# ra-08h_development_board_V1_0-20230228.net
KiCad netlist of a schematic drawn in EAGLE
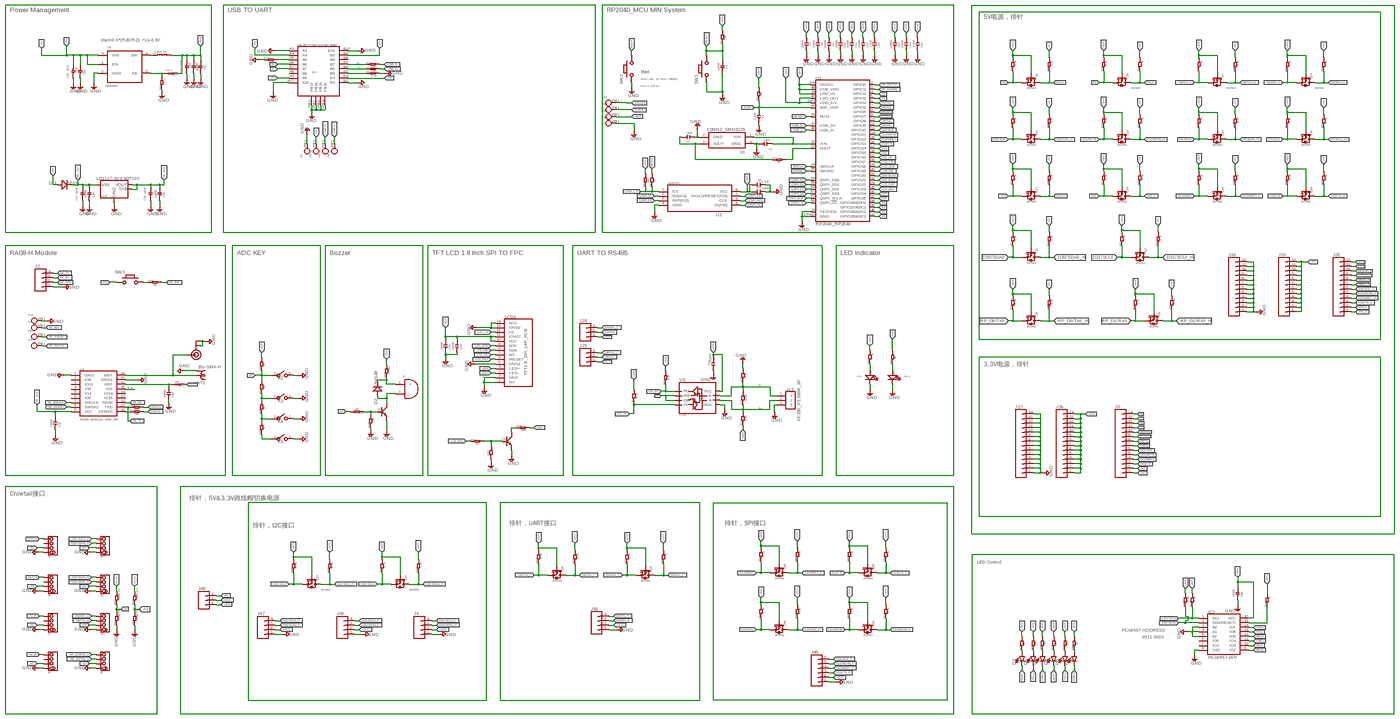
[diagram p0: schematic, sheet 1, overview]
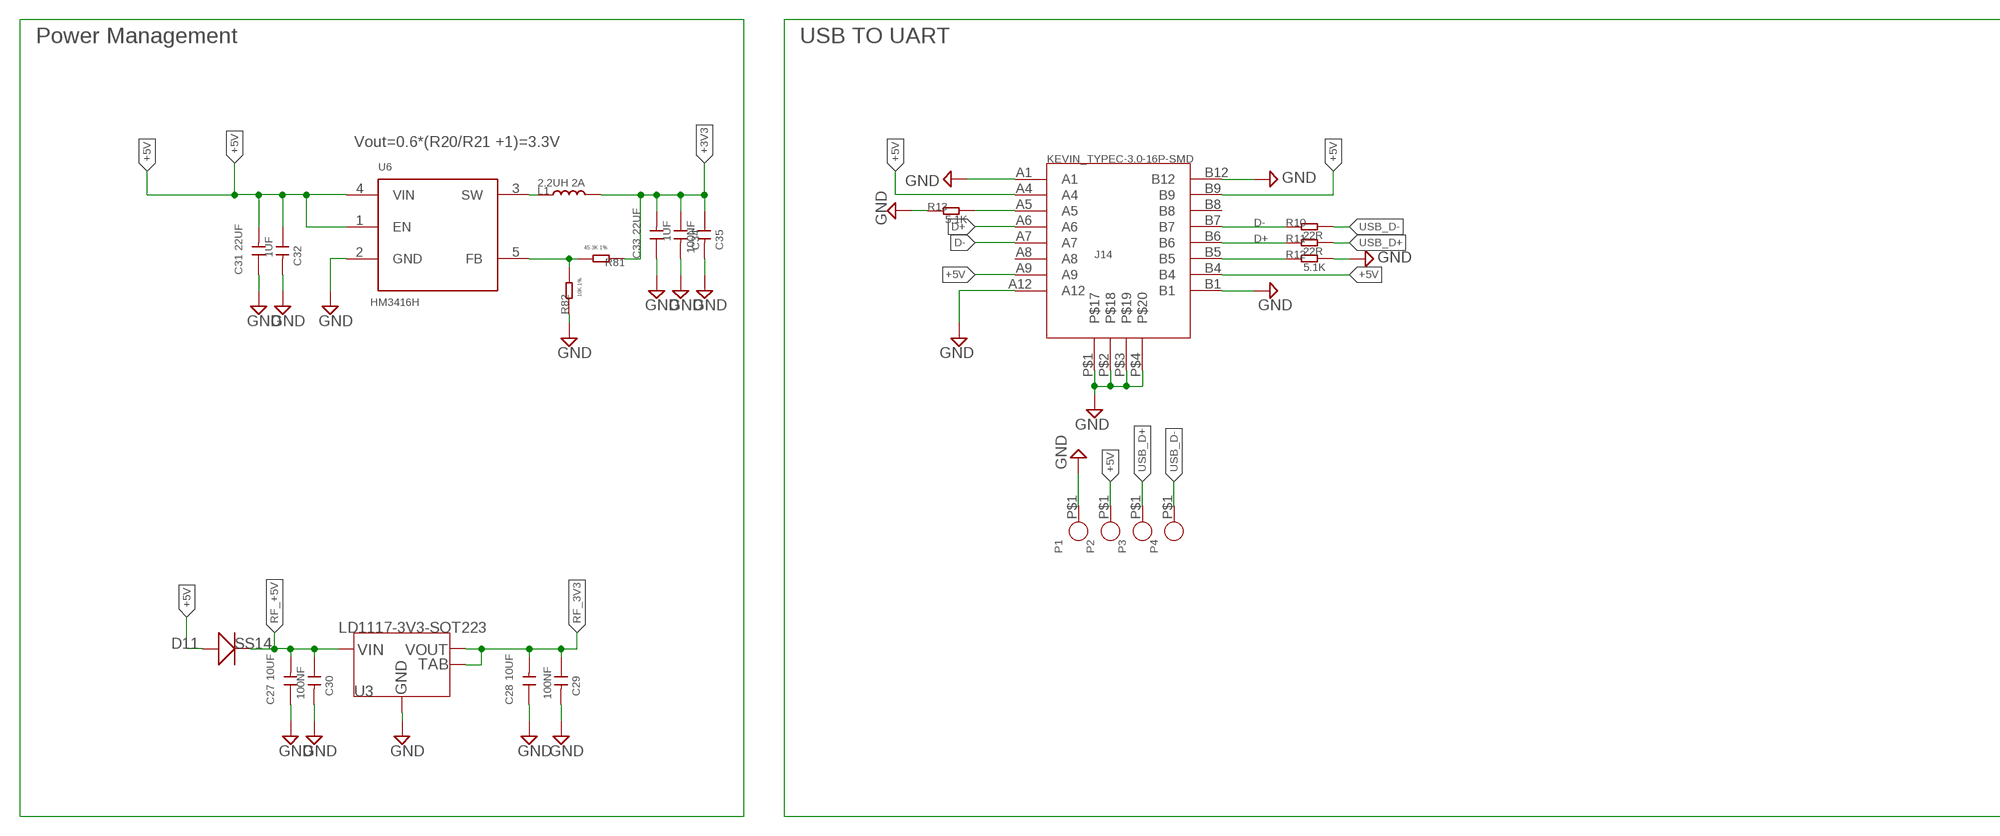
[diagram p1: schematic, sheet 1, part 1 of 6]
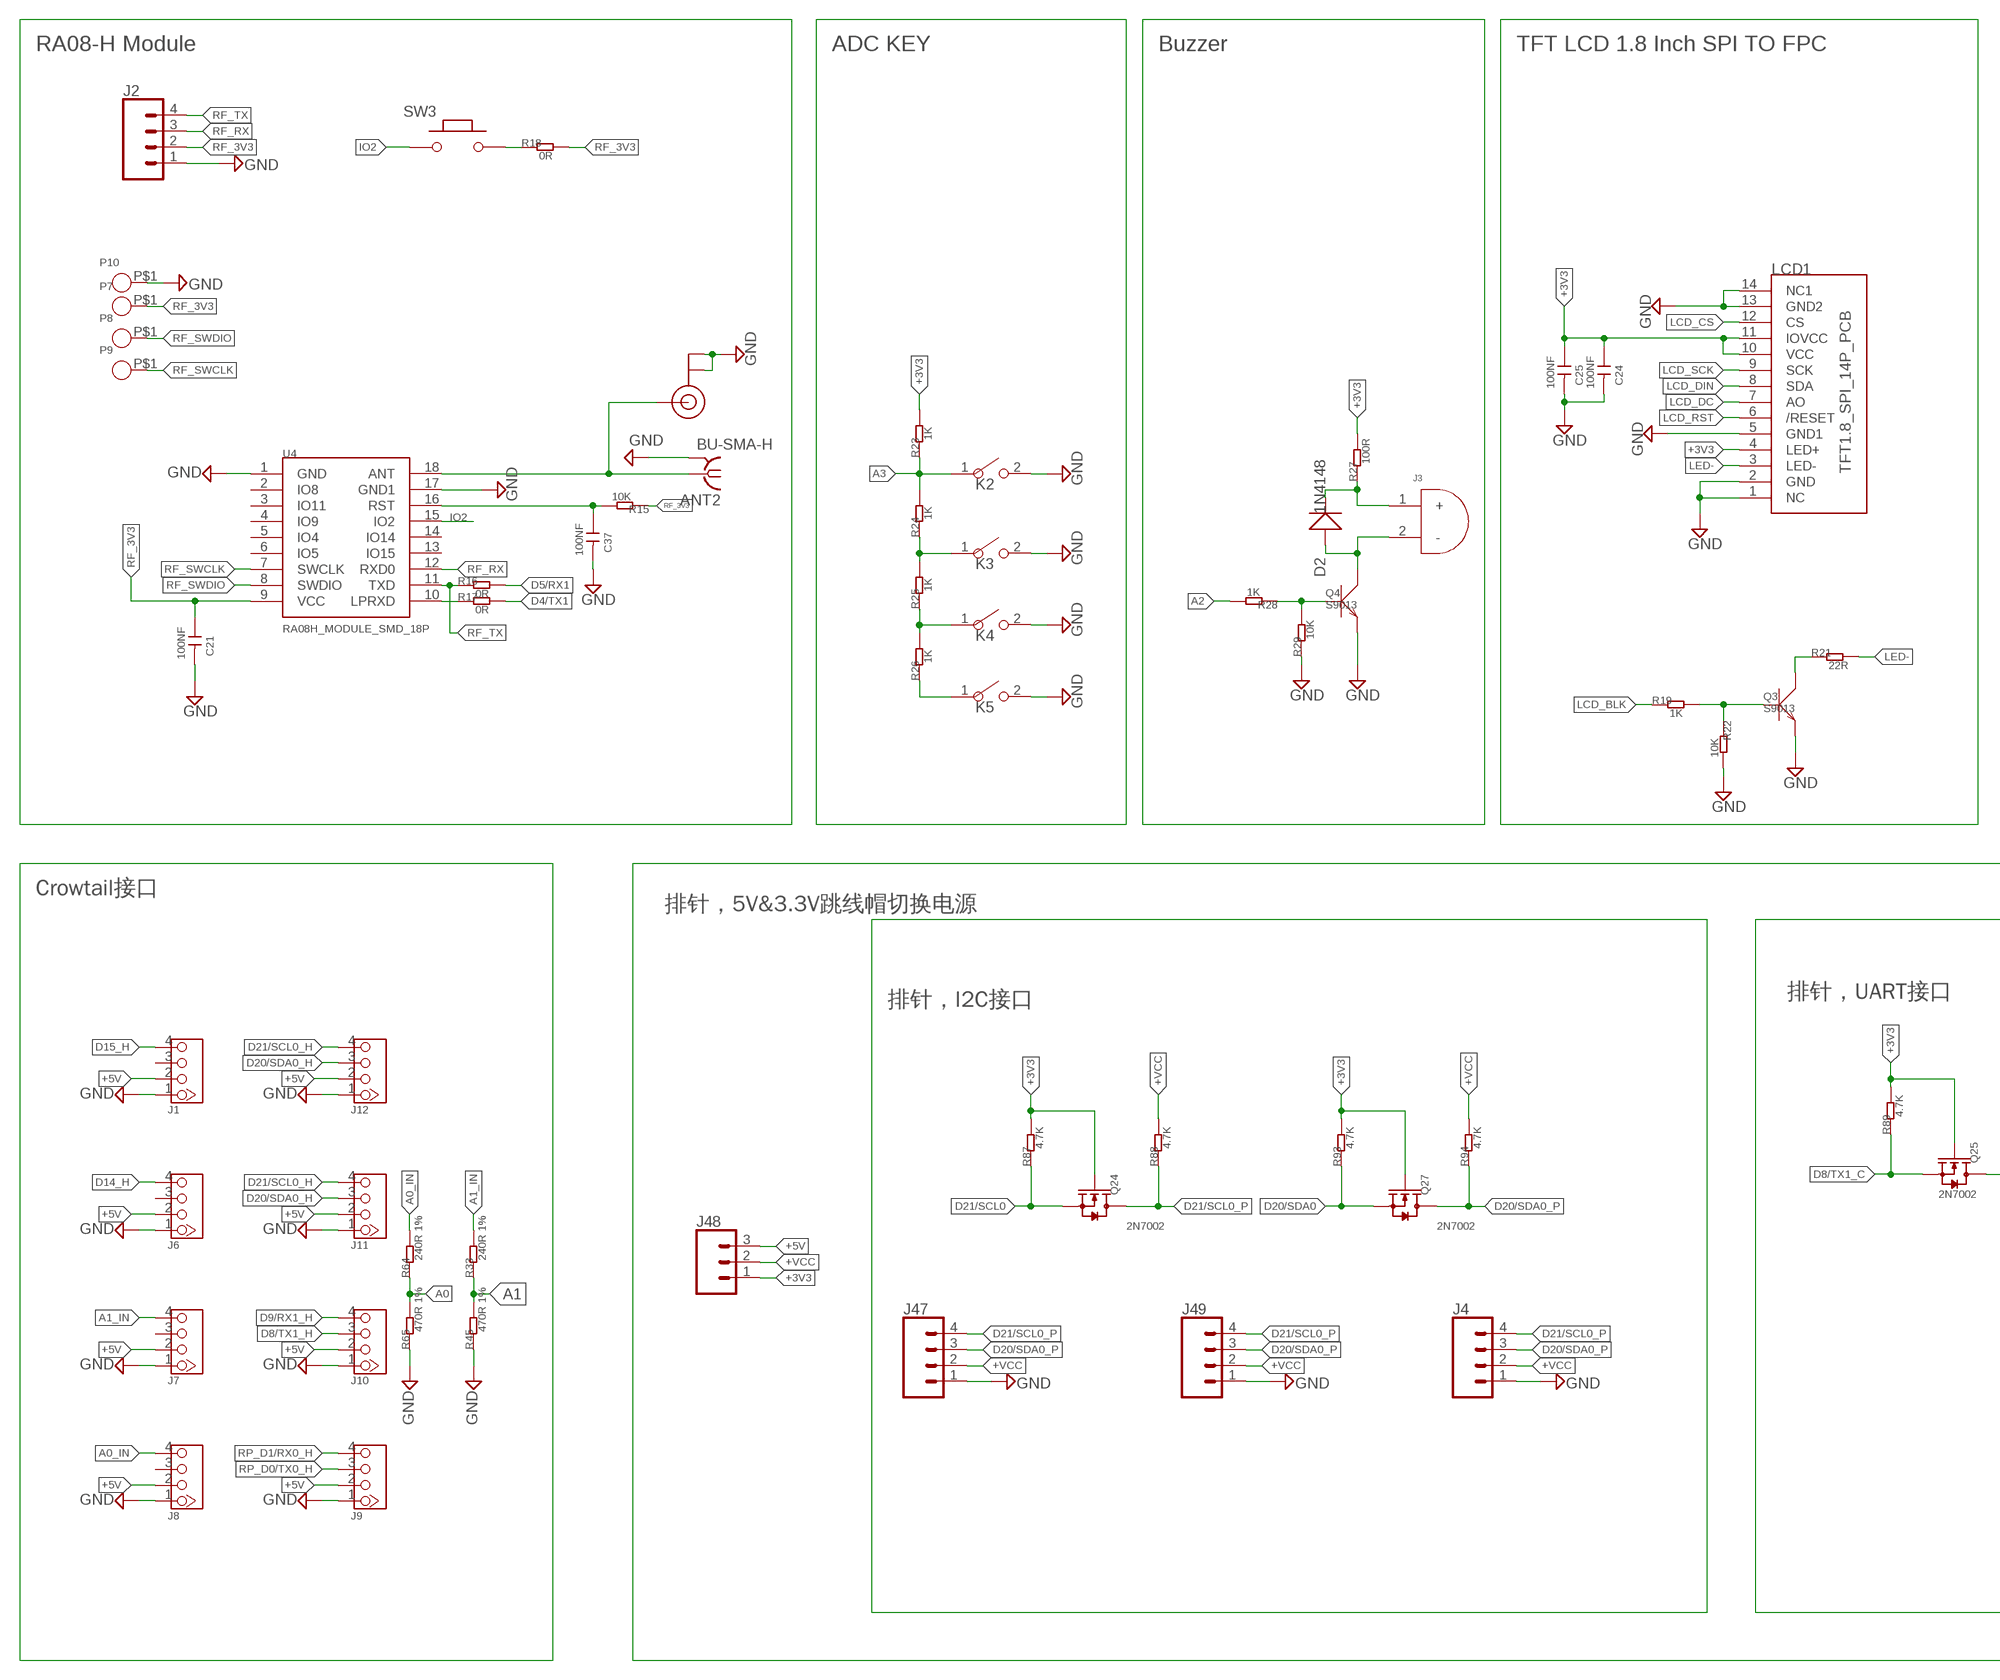
[diagram p2: schematic, sheet 1, part 2 of 6]
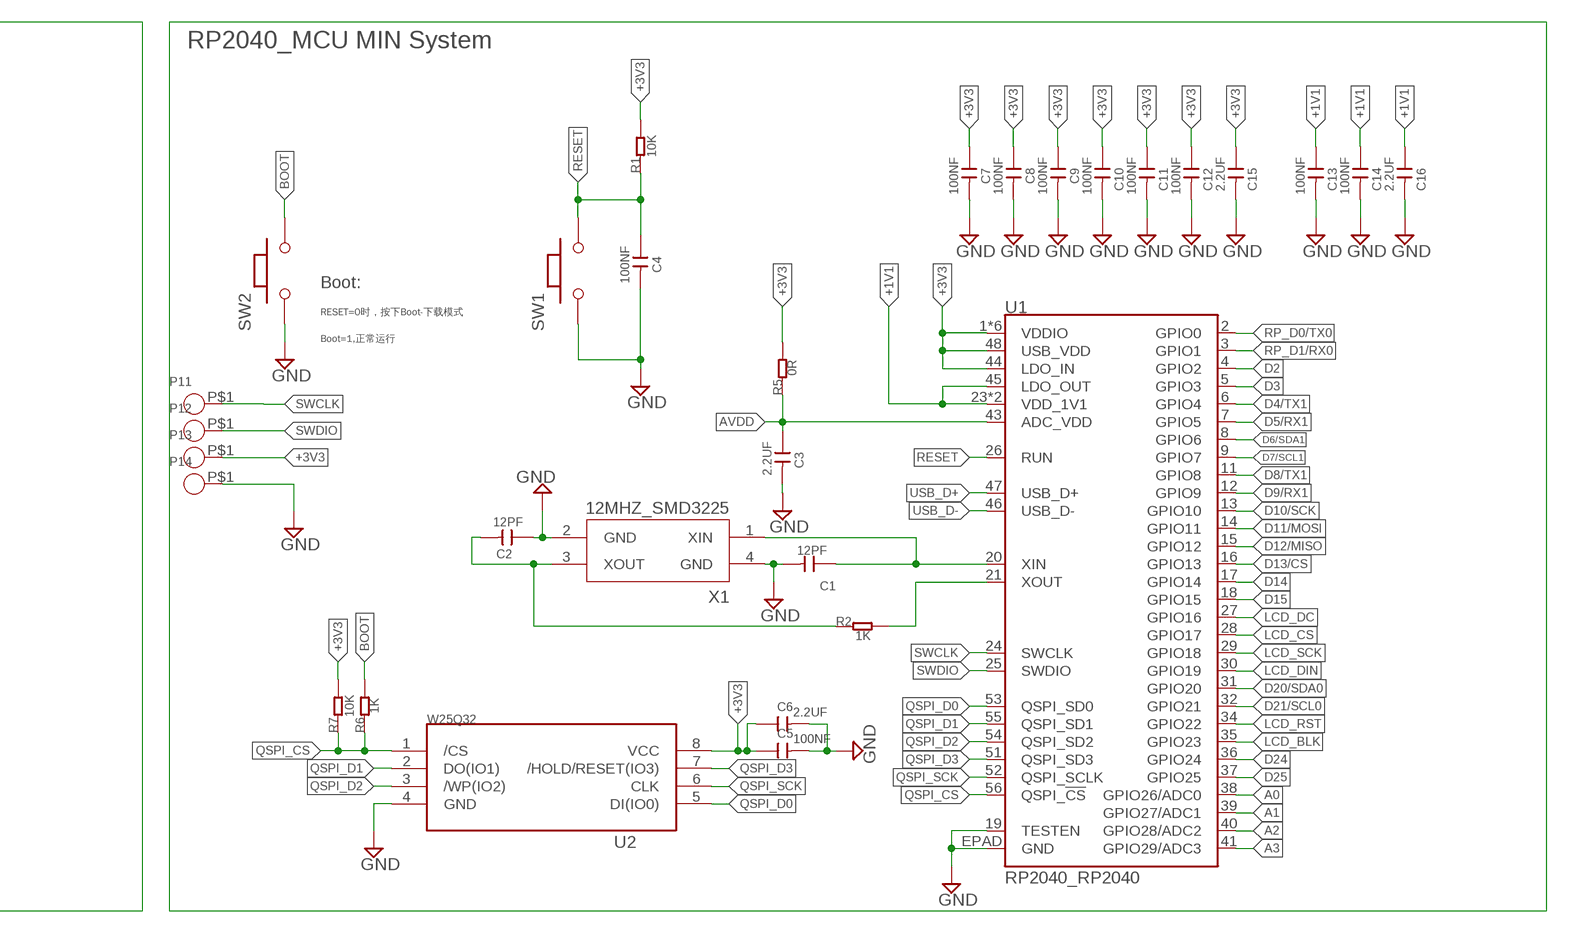
[diagram p3: schematic, sheet 1, part 3 of 6]
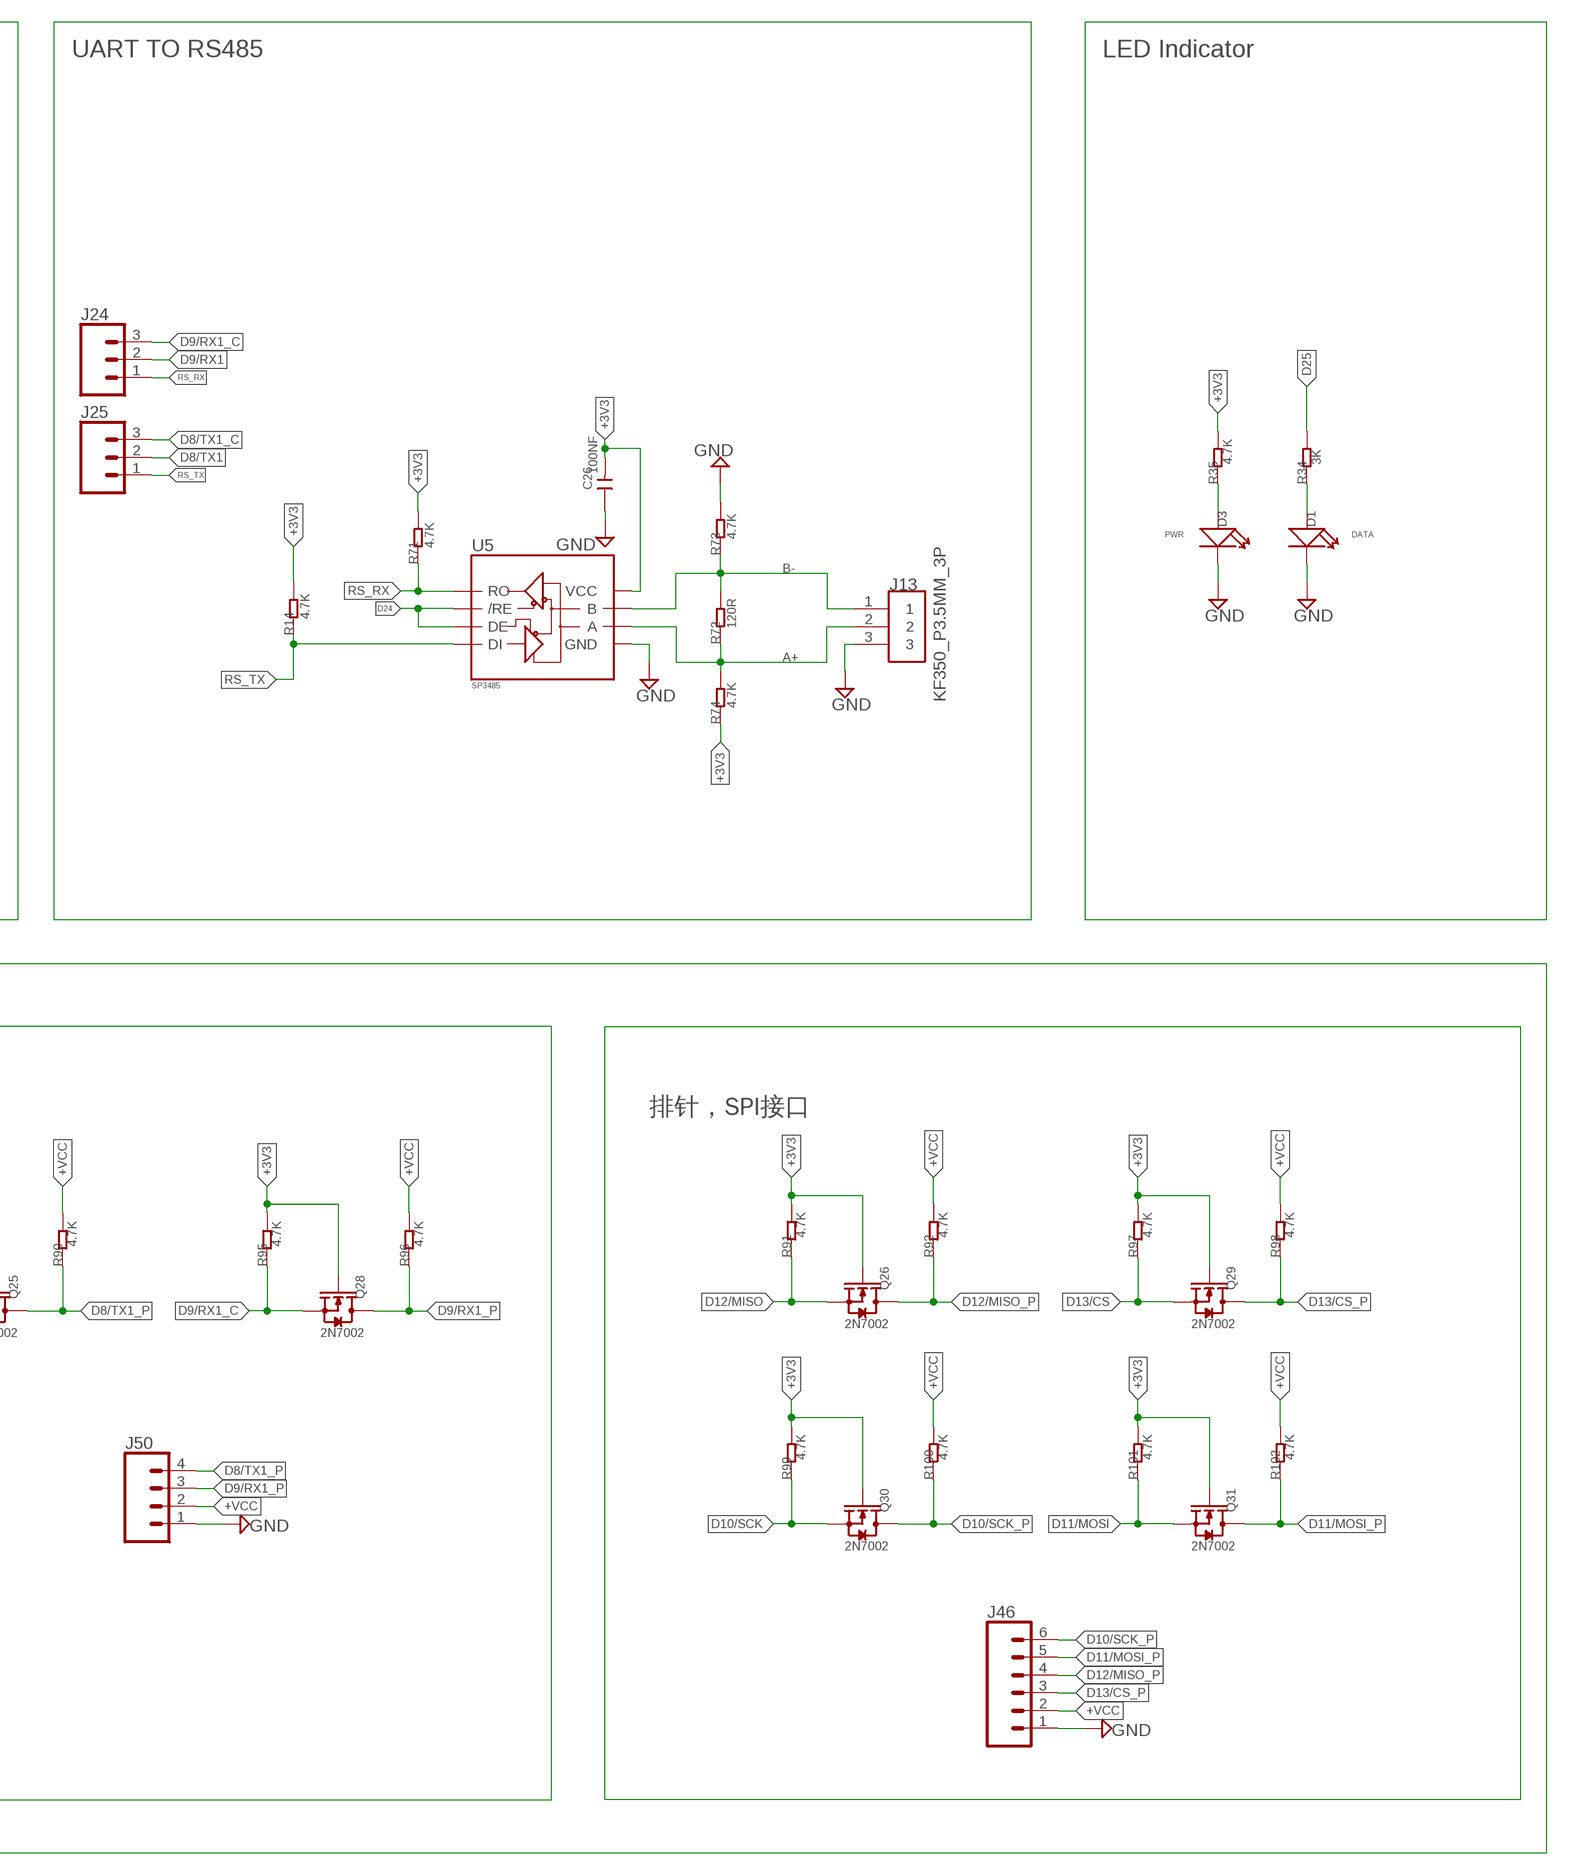
[diagram p4: schematic, sheet 1, part 4 of 6]
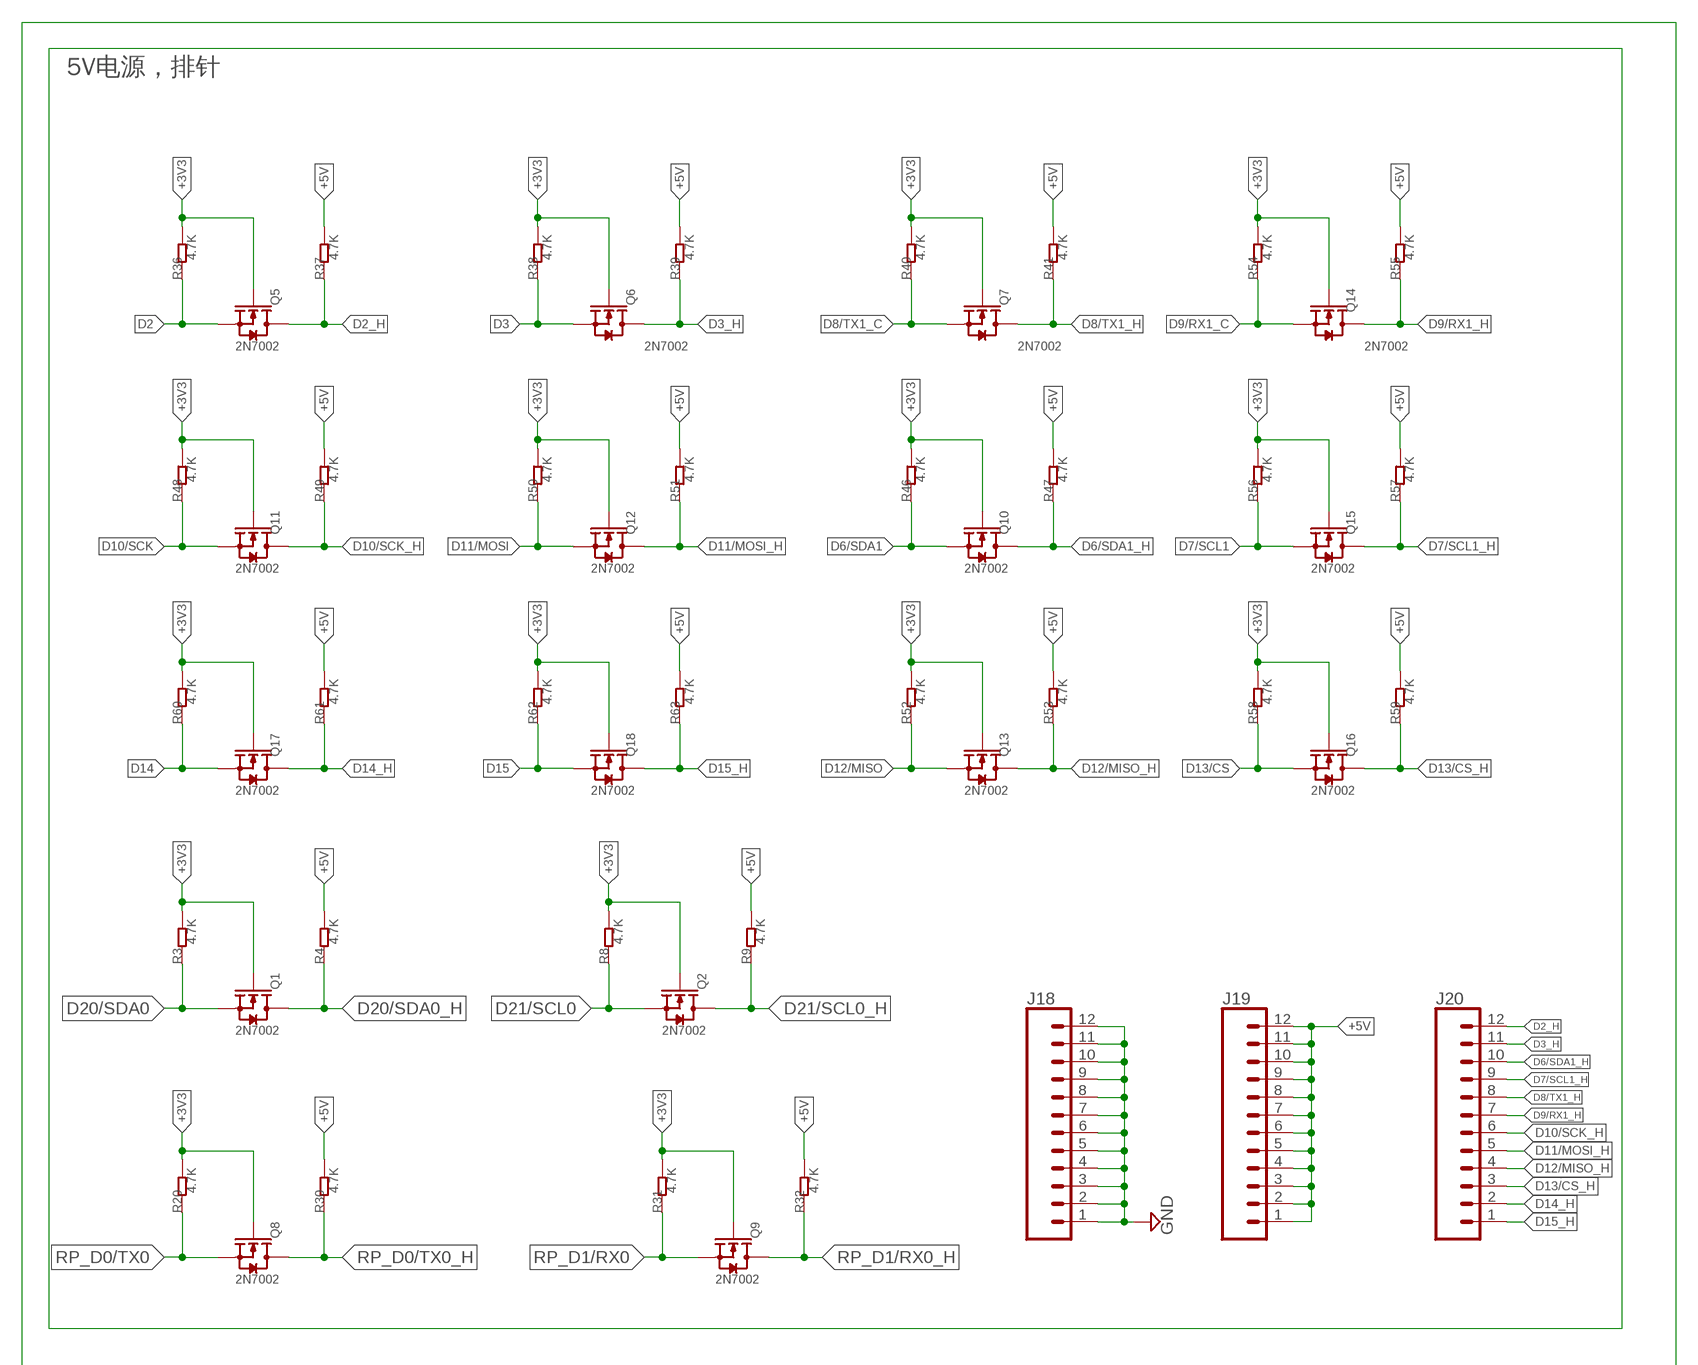
[diagram p5: schematic, sheet 1, part 5 of 6]
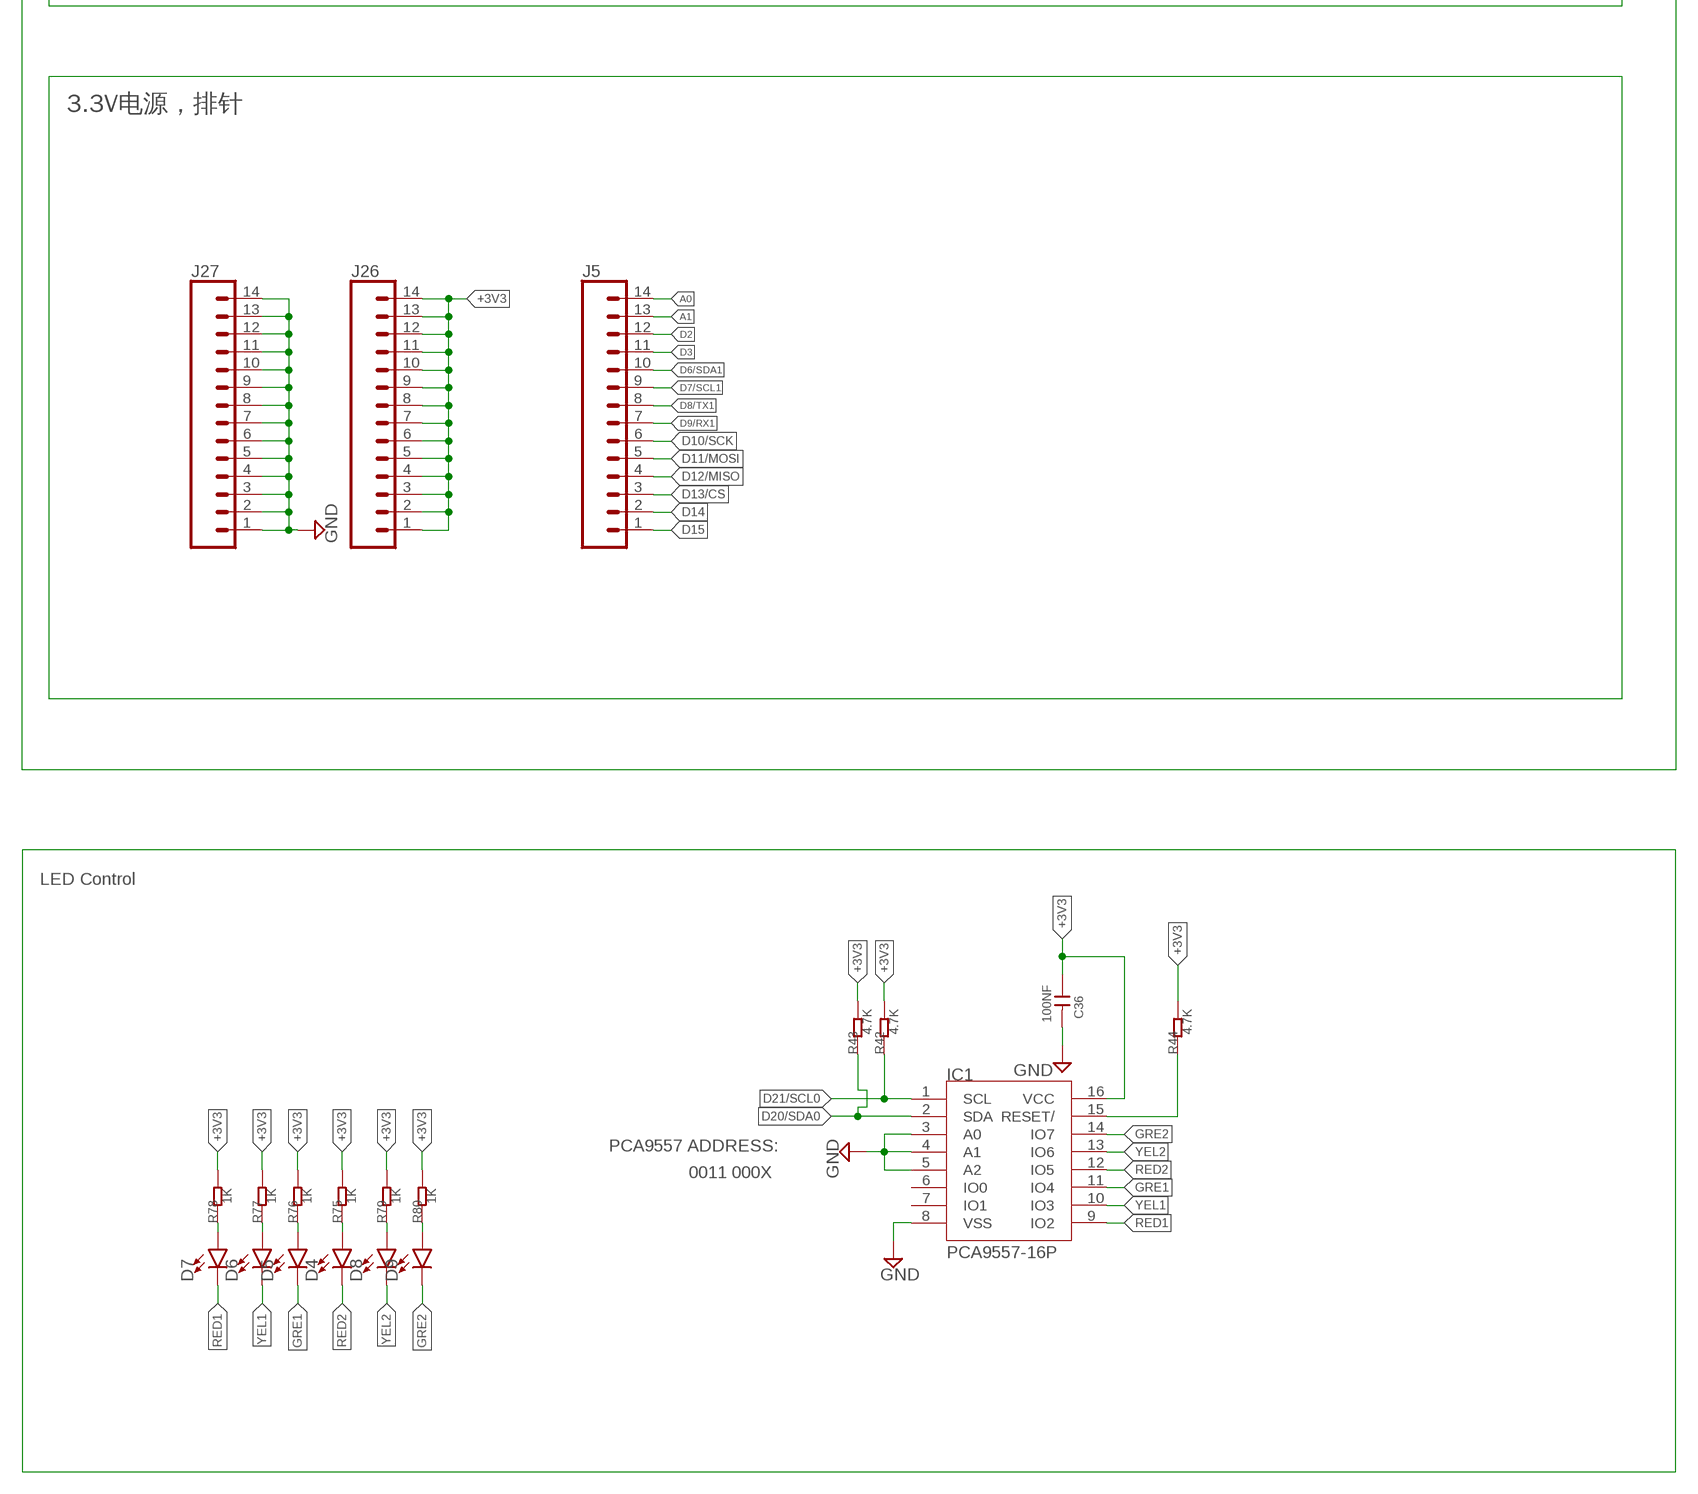
[diagram p6: schematic, sheet 1, part 6 of 6]

(export (version "E")
  (design (tool "Eeschema 10.0.6"))
  (components
    (comp (ref "ANT1")
      (value "SPARKFUN2_U.FL")
      (footprint "eagle-import:SPARKFUN2_U.FL")
      (libsource (lib "eagle-import") (part "SPARKFUN2_U.FL"))
    )
    (comp (ref "ANT2")
      (value "BU-SMA-H")
      (footprint "eagle-import:BU-SMA-H")
      (libsource (lib "eagle-import") (part "BU-SMA-H"))
    )
    (comp (ref "C1")
      (value "12PF")
      (footprint "eagle-import:A_XBJ_0603")
      (libsource (lib "eagle-import") (part "A_XBJ_C0603"))
    )
    (comp (ref "C2")
      (value "12PF")
      (footprint "eagle-import:A_XBJ_0603")
      (libsource (lib "eagle-import") (part "A_XBJ_C0603"))
    )
    (comp (ref "C3")
      (value "2.2UF")
      (footprint "eagle-import:A_XBJ_0603")
      (libsource (lib "eagle-import") (part "A_XBJ_C0603"))
    )
    (comp (ref "C4")
      (value "100NF")
      (footprint "eagle-import:A_XBJ_0603")
      (libsource (lib "eagle-import") (part "A_XBJ_C0603"))
    )
    (comp (ref "C5")
      (value "100NF")
      (footprint "eagle-import:A_XBJ_0603")
      (libsource (lib "eagle-import") (part "A_XBJ_C0603"))
    )
    (comp (ref "C6")
      (value "2.2UF")
      (footprint "eagle-import:A_XBJ_0603")
      (libsource (lib "eagle-import") (part "A_XBJ_C0603"))
    )
    (comp (ref "C7")
      (value "100NF")
      (footprint "eagle-import:A_XBJ_0603")
      (libsource (lib "eagle-import") (part "A_XBJ_C0603"))
    )
    (comp (ref "C8")
      (value "100NF")
      (footprint "eagle-import:A_XBJ_0603")
      (libsource (lib "eagle-import") (part "A_XBJ_C0603"))
    )
    (comp (ref "C9")
      (value "100NF")
      (footprint "eagle-import:A_XBJ_0603")
      (libsource (lib "eagle-import") (part "A_XBJ_C0603"))
    )
    (comp (ref "C10")
      (value "100NF")
      (footprint "eagle-import:A_XBJ_0603")
      (libsource (lib "eagle-import") (part "A_XBJ_C0603"))
    )
    (comp (ref "C11")
      (value "100NF")
      (footprint "eagle-import:A_XBJ_0603")
      (libsource (lib "eagle-import") (part "A_XBJ_C0603"))
    )
    (comp (ref "C12")
      (value "100NF")
      (footprint "eagle-import:A_XBJ_0603")
      (libsource (lib "eagle-import") (part "A_XBJ_C0603"))
    )
    (comp (ref "C13")
      (value "100NF")
      (footprint "eagle-import:A_XBJ_0603")
      (libsource (lib "eagle-import") (part "A_XBJ_C0603"))
    )
    (comp (ref "C14")
      (value "100NF")
      (footprint "eagle-import:A_XBJ_0603")
      (libsource (lib "eagle-import") (part "A_XBJ_C0603"))
    )
    (comp (ref "C15")
      (value "2.2UF")
      (footprint "eagle-import:A_XBJ_0603")
      (libsource (lib "eagle-import") (part "A_XBJ_C0603"))
    )
    (comp (ref "C16")
      (value "2.2UF")
      (footprint "eagle-import:A_XBJ_0603")
      (libsource (lib "eagle-import") (part "A_XBJ_C0603"))
    )
    (comp (ref "C21")
      (value "100NF")
      (footprint "eagle-import:A_XBJ_0603")
      (libsource (lib "eagle-import") (part "A_XBJ_C0603"))
    )
    (comp (ref "C24")
      (value "100NF")
      (footprint "eagle-import:A_XBJ_0603")
      (libsource (lib "eagle-import") (part "A_XBJ_C0603"))
    )
    (comp (ref "C25")
      (value "100NF")
      (footprint "eagle-import:A_XBJ_0603")
      (libsource (lib "eagle-import") (part "A_XBJ_C0603"))
    )
    (comp (ref "C26")
      (value "100NF")
      (footprint "eagle-import:A_XBJ_0603")
      (libsource (lib "eagle-import") (part "A_XBJ_C0603"))
    )
    (comp (ref "C27")
      (value "10UF")
      (footprint "eagle-import:A_XBJ_0805")
      (libsource (lib "eagle-import") (part "A_XBJ_C0805"))
    )
    (comp (ref "C28")
      (value "10UF")
      (footprint "eagle-import:A_XBJ_0805")
      (libsource (lib "eagle-import") (part "A_XBJ_C0805"))
    )
    (comp (ref "C29")
      (value "100NF")
      (footprint "eagle-import:A_XBJ_0603")
      (libsource (lib "eagle-import") (part "A_XBJ_C0603"))
    )
    (comp (ref "C30")
      (value "100NF")
      (footprint "eagle-import:A_XBJ_0603")
      (libsource (lib "eagle-import") (part "A_XBJ_C0603"))
    )
    (comp (ref "C31")
      (value "22UF")
      (footprint "eagle-import:A_XBJ_0805")
      (libsource (lib "eagle-import") (part "A_XBJ_C0805"))
    )
    (comp (ref "C32")
      (value "1UF")
      (footprint "eagle-import:A_XBJ_0603")
      (libsource (lib "eagle-import") (part "A_XBJ_C0603"))
    )
    (comp (ref "C33")
      (value "22UF")
      (footprint "eagle-import:A_XBJ_0805")
      (libsource (lib "eagle-import") (part "A_XBJ_C0805"))
    )
    (comp (ref "C34")
      (value "1UF")
      (footprint "eagle-import:A_XBJ_0603")
      (libsource (lib "eagle-import") (part "A_XBJ_C0603"))
    )
    (comp (ref "C35")
      (value "100NF")
      (footprint "eagle-import:A_XBJ_0603")
      (libsource (lib "eagle-import") (part "A_XBJ_C0603"))
    )
    (comp (ref "C36")
      (value "100NF")
      (footprint "eagle-import:A_XBJ_0603")
      (libsource (lib "eagle-import") (part "A_XBJ_C0603"))
    )
    (comp (ref "C37")
      (value "100NF")
      (footprint "eagle-import:A_XBJ_0603")
      (libsource (lib "eagle-import") (part "A_XBJ_C0603"))
    )
    (comp (ref "D1")
      (value "DISCRETE_007-LED0603")
      (footprint "eagle-import:DISCRETE_D0603")
      (libsource (lib "eagle-import") (part "DISCRETE_007-LED0603"))
    )
    (comp (ref "D2")
      (value "1N4148")
      (footprint "eagle-import:DISCRETE_DO-35-SMD")
      (libsource (lib "eagle-import") (part "DISCRETE_D1N4148-SMD"))
    )
    (comp (ref "D3")
      (value "DISCRETE_007-LED0603")
      (footprint "eagle-import:DISCRETE_D0603")
      (libsource (lib "eagle-import") (part "DISCRETE_007-LED0603"))
    )
    (comp (ref "D4")
      (value "LED-3MM-NO_SILK")
      (footprint "eagle-import:LED_3MM-NS")
      (libsource (lib "eagle-import") (part "LED-3MM-NO_SILK"))
    )
    (comp (ref "D5")
      (value "LED-3MM-NO_SILK")
      (footprint "eagle-import:LED_3MM-NS")
      (libsource (lib "eagle-import") (part "LED-3MM-NO_SILK"))
    )
    (comp (ref "D6")
      (value "LED-3MM-NO_SILK")
      (footprint "eagle-import:LED_3MM-NS")
      (libsource (lib "eagle-import") (part "LED-3MM-NO_SILK"))
    )
    (comp (ref "D7")
      (value "LED-3MM-NO_SILK")
      (footprint "eagle-import:LED_3MM-NS")
      (libsource (lib "eagle-import") (part "LED-3MM-NO_SILK"))
    )
    (comp (ref "D8")
      (value "LED-3MM-NO_SILK")
      (footprint "eagle-import:LED_3MM-NS")
      (libsource (lib "eagle-import") (part "LED-3MM-NO_SILK"))
    )
    (comp (ref "D9")
      (value "LED-3MM-NO_SILK")
      (footprint "eagle-import:LED_3MM-NS")
      (libsource (lib "eagle-import") (part "LED-3MM-NO_SILK"))
    )
    (comp (ref "D11")
      (value "SS14")
      (footprint "eagle-import:DISCRETE_D2010")
      (libsource (lib "eagle-import") (part "DISCRETE_DSMA"))
    )
    (comp (ref "IC1")
      (value "PCA9557-16P")
      (footprint "eagle-import:TSSOP16")
      (libsource (lib "eagle-import") (part "PCA9557-16P"))
    )
    (comp (ref "J1")
      (value "CONNECTER_TWIG_2.0")
      (footprint "eagle-import:CONNECTER_2.0_1X4")
      (libsource (lib "eagle-import") (part "CONNECTER_TWIG_2.0"))
    )
    (comp (ref "J2")
      (value "CONN_04PTH")
      (footprint "eagle-import:1X04")
      (libsource (lib "eagle-import") (part "CONN_04PTH"))
    )
    (comp (ref "J3")
      (value "A_XBJ_MLT-8530")
      (footprint "eagle-import:A_XBJ_MLT-8530")
      (libsource (lib "eagle-import") (part "A_XBJ_MLT-8530"))
    )
    (comp (ref "J4")
      (value "CONN_04PTH")
      (footprint "eagle-import:1X04")
      (libsource (lib "eagle-import") (part "CONN_04PTH"))
    )
    (comp (ref "J5")
      (value "CONN_14")
      (footprint "eagle-import:1X14")
      (libsource (lib "eagle-import") (part "CONN_14"))
    )
    (comp (ref "J6")
      (value "CONNECTER_TWIG_2.0")
      (footprint "eagle-import:CONNECTER_2.0_1X4")
      (libsource (lib "eagle-import") (part "CONNECTER_TWIG_2.0"))
    )
    (comp (ref "J7")
      (value "CONNECTER_TWIG_2.0")
      (footprint "eagle-import:CONNECTER_2.0_1X4")
      (libsource (lib "eagle-import") (part "CONNECTER_TWIG_2.0"))
    )
    (comp (ref "J8")
      (value "CONNECTER_TWIG_2.0")
      (footprint "eagle-import:CONNECTER_2.0_1X4")
      (libsource (lib "eagle-import") (part "CONNECTER_TWIG_2.0"))
    )
    (comp (ref "J9")
      (value "CONNECTER_TWIG_2.0")
      (footprint "eagle-import:CONNECTER_2.0_1X4")
      (libsource (lib "eagle-import") (part "CONNECTER_TWIG_2.0"))
    )
    (comp (ref "J10")
      (value "CONNECTER_TWIG_2.0")
      (footprint "eagle-import:CONNECTER_2.0_1X4")
      (libsource (lib "eagle-import") (part "CONNECTER_TWIG_2.0"))
    )
    (comp (ref "J11")
      (value "CONNECTER_TWIG_2.0")
      (footprint "eagle-import:CONNECTER_2.0_1X4")
      (libsource (lib "eagle-import") (part "CONNECTER_TWIG_2.0"))
    )
    (comp (ref "J12")
      (value "CONNECTER_TWIG_2.0")
      (footprint "eagle-import:CONNECTER_2.0_1X4")
      (libsource (lib "eagle-import") (part "CONNECTER_TWIG_2.0"))
    )
    (comp (ref "J13")
      (value "KF350_P3.5MM_3P")
      (footprint "eagle-import:KF350_P3.5MM_3P")
      (libsource (lib "eagle-import") (part "KF350_P3.5MM_3P"))
    )
    (comp (ref "J14")
      (value "KEVIN_TYPEC-3.0-16P-SMD")
      (footprint "eagle-import:KEVIN_3.0TYPEC-SMD")
      (libsource (lib "eagle-import") (part "KEVIN_TYPEC-3.0-16P-SMD"))
    )
    (comp (ref "J18")
      (value "CONN_12")
      (footprint "eagle-import:1X12")
      (libsource (lib "eagle-import") (part "CONN_12"))
    )
    (comp (ref "J19")
      (value "CONN_12")
      (footprint "eagle-import:1X12")
      (libsource (lib "eagle-import") (part "CONN_12"))
    )
    (comp (ref "J20")
      (value "CONN_12")
      (footprint "eagle-import:1X12")
      (libsource (lib "eagle-import") (part "CONN_12"))
    )
    (comp (ref "J24")
      (value "455-1750-1-ND")
      (footprint "eagle-import:1X03")
      (libsource (lib "eagle-import") (part "CONN_03"))
    )
    (comp (ref "J25")
      (value "455-1750-1-ND")
      (footprint "eagle-import:1X03")
      (libsource (lib "eagle-import") (part "CONN_03"))
    )
    (comp (ref "J26")
      (value "CONN_14")
      (footprint "eagle-import:1X14")
      (libsource (lib "eagle-import") (part "CONN_14"))
    )
    (comp (ref "J27")
      (value "CONN_14")
      (footprint "eagle-import:1X14")
      (libsource (lib "eagle-import") (part "CONN_14"))
    )
    (comp (ref "J46")
      (value "CONN_06SILK_FEMALE_PTH")
      (footprint "eagle-import:1X06")
      (libsource (lib "eagle-import") (part "CONN_06SILK_FEMALE_PTH"))
    )
    (comp (ref "J47")
      (value "CONN_04PTH")
      (footprint "eagle-import:1X04")
      (libsource (lib "eagle-import") (part "CONN_04PTH"))
    )
    (comp (ref "J48")
      (value "455-1750-1-ND")
      (footprint "eagle-import:1X03")
      (libsource (lib "eagle-import") (part "CONN_03"))
    )
    (comp (ref "J49")
      (value "CONN_04PTH")
      (footprint "eagle-import:1X04")
      (libsource (lib "eagle-import") (part "CONN_04PTH"))
    )
    (comp (ref "J50")
      (value "CONN_04PTH")
      (footprint "eagle-import:1X04")
      (libsource (lib "eagle-import") (part "CONN_04PTH"))
    )
    (comp (ref "K2")
      (value "CROWBO_KEY_2PIN_6.5X3.5")
      (footprint "eagle-import:CROWBOT_-V1.2-20220713_CROWBOT-V1.1库_KEY_EN_2PIN_B_W")
      (libsource (lib "eagle-import") (part "CROWBO_KEY_2PIN_6.5X3.5"))
    )
    (comp (ref "K3")
      (value "CROWBO_KEY_2PIN_6.5X3.5")
      (footprint "eagle-import:CROWBOT_-V1.2-20220713_CROWBOT-V1.1库_KEY_EN_2PIN_B_W")
      (libsource (lib "eagle-import") (part "CROWBO_KEY_2PIN_6.5X3.5"))
    )
    (comp (ref "K4")
      (value "CROWBO_KEY_2PIN_6.5X3.5")
      (footprint "eagle-import:CROWBOT_-V1.2-20220713_CROWBOT-V1.1库_KEY_EN_2PIN_B_W")
      (libsource (lib "eagle-import") (part "CROWBO_KEY_2PIN_6.5X3.5"))
    )
    (comp (ref "K5")
      (value "CROWBO_KEY_2PIN_6.5X3.5")
      (footprint "eagle-import:CROWBOT_-V1.2-20220713_CROWBOT-V1.1库_KEY_EN_2PIN_B_W")
      (libsource (lib "eagle-import") (part "CROWBO_KEY_2PIN_6.5X3.5"))
    )
    (comp (ref "L1")
      (value "2.2UH 2A")
      (footprint "eagle-import:CROWPI_POW_L773")
      (libsource (lib "eagle-import") (part "DISCRETE_LL773"))
    )
    (comp (ref "LCD1")
      (value "TFT1.8_SPI_14P_PCB")
      (footprint "eagle-import:TFF1.8_SPI_14P_PCB")
      (libsource (lib "eagle-import") (part "TFT1.8_SPI_14P_PCB"))
    )
    (comp (ref "P1")
      (value "CROWPI_POW_PADPAD-1.0MM")
      (footprint "eagle-import:CROWPI_POW_PAD-1.0MM")
      (libsource (lib "eagle-import") (part "CROWPI_POW_PADPAD-1.0MM"))
    )
    (comp (ref "P2")
      (value "CROWPI_POW_PADPAD-1.0MM")
      (footprint "eagle-import:CROWPI_POW_PAD-1.0MM")
      (libsource (lib "eagle-import") (part "CROWPI_POW_PADPAD-1.0MM"))
    )
    (comp (ref "P3")
      (value "CROWPI_POW_PADPAD-1.0MM")
      (footprint "eagle-import:CROWPI_POW_PAD-1.0MM")
      (libsource (lib "eagle-import") (part "CROWPI_POW_PADPAD-1.0MM"))
    )
    (comp (ref "P4")
      (value "CROWPI_POW_PADPAD-1.0MM")
      (footprint "eagle-import:CROWPI_POW_PAD-1.0MM")
      (libsource (lib "eagle-import") (part "CROWPI_POW_PADPAD-1.0MM"))
    )
    (comp (ref "P7")
      (value "CROWPI_POW_PADPAD-1.0MM")
      (footprint "eagle-import:CROWPI_POW_PAD-1.0MM")
      (libsource (lib "eagle-import") (part "CROWPI_POW_PADPAD-1.0MM"))
    )
    (comp (ref "P8")
      (value "CROWPI_POW_PADPAD-1.0MM")
      (footprint "eagle-import:CROWPI_POW_PAD-1.0MM")
      (libsource (lib "eagle-import") (part "CROWPI_POW_PADPAD-1.0MM"))
    )
    (comp (ref "P9")
      (value "CROWPI_POW_PADPAD-1.0MM")
      (footprint "eagle-import:CROWPI_POW_PAD-1.0MM")
      (libsource (lib "eagle-import") (part "CROWPI_POW_PADPAD-1.0MM"))
    )
    (comp (ref "P10")
      (value "CROWPI_POW_PADPAD-1.0MM")
      (footprint "eagle-import:CROWPI_POW_PAD-1.0MM")
      (libsource (lib "eagle-import") (part "CROWPI_POW_PADPAD-1.0MM"))
    )
    (comp (ref "P11")
      (value "CROWPI_POW_PADPAD-1.0MM")
      (footprint "eagle-import:CROWPI_POW_PAD-1.0MM")
      (libsource (lib "eagle-import") (part "CROWPI_POW_PADPAD-1.0MM"))
    )
    (comp (ref "P12")
      (value "CROWPI_POW_PADPAD-1.0MM")
      (footprint "eagle-import:CROWPI_POW_PAD-1.0MM")
      (libsource (lib "eagle-import") (part "CROWPI_POW_PADPAD-1.0MM"))
    )
    (comp (ref "P13")
      (value "CROWPI_POW_PADPAD-1.0MM")
      (footprint "eagle-import:CROWPI_POW_PAD-1.0MM")
      (libsource (lib "eagle-import") (part "CROWPI_POW_PADPAD-1.0MM"))
    )
    (comp (ref "P14")
      (value "CROWPI_POW_PADPAD-1.0MM")
      (footprint "eagle-import:CROWPI_POW_PAD-1.0MM")
      (libsource (lib "eagle-import") (part "CROWPI_POW_PADPAD-1.0MM"))
    )
    (comp (ref "Q1")
      (value "2N7002")
      (footprint "eagle-import:DISCRETE_SOT23")
      (libsource (lib "eagle-import") (part "DISCRETE_MOSFET-NSOT23"))
    )
    (comp (ref "Q2")
      (value "2N7002")
      (footprint "eagle-import:DISCRETE_SOT23")
      (libsource (lib "eagle-import") (part "DISCRETE_MOSFET-NSOT23"))
    )
    (comp (ref "Q3")
      (value "S9013")
      (footprint "eagle-import:DISCRETE_SOT23$1")
      (libsource (lib "eagle-import") (part "DISCRETE_TRANSISTOR-NPN-SOT23"))
    )
    (comp (ref "Q4")
      (value "S9013")
      (footprint "eagle-import:DISCRETE_SOT23$1")
      (libsource (lib "eagle-import") (part "DISCRETE_TRANSISTOR-NPN-SOT23"))
    )
    (comp (ref "Q5")
      (value "2N7002")
      (footprint "eagle-import:DISCRETE_SOT23")
      (libsource (lib "eagle-import") (part "DISCRETE_MOSFET-NSOT23"))
    )
    (comp (ref "Q6")
      (value "2N7002")
      (footprint "eagle-import:DISCRETE_SOT23")
      (libsource (lib "eagle-import") (part "DISCRETE_MOSFET-NSOT23"))
    )
    (comp (ref "Q7")
      (value "2N7002")
      (footprint "eagle-import:DISCRETE_SOT23")
      (libsource (lib "eagle-import") (part "DISCRETE_MOSFET-NSOT23"))
    )
    (comp (ref "Q8")
      (value "2N7002")
      (footprint "eagle-import:DISCRETE_SOT23")
      (libsource (lib "eagle-import") (part "DISCRETE_MOSFET-NSOT23"))
    )
    (comp (ref "Q9")
      (value "2N7002")
      (footprint "eagle-import:DISCRETE_SOT23")
      (libsource (lib "eagle-import") (part "DISCRETE_MOSFET-NSOT23"))
    )
    (comp (ref "Q10")
      (value "2N7002")
      (footprint "eagle-import:DISCRETE_SOT23")
      (libsource (lib "eagle-import") (part "DISCRETE_MOSFET-NSOT23"))
    )
    (comp (ref "Q11")
      (value "2N7002")
      (footprint "eagle-import:DISCRETE_SOT23")
      (libsource (lib "eagle-import") (part "DISCRETE_MOSFET-NSOT23"))
    )
    (comp (ref "Q12")
      (value "2N7002")
      (footprint "eagle-import:DISCRETE_SOT23")
      (libsource (lib "eagle-import") (part "DISCRETE_MOSFET-NSOT23"))
    )
    (comp (ref "Q13")
      (value "2N7002")
      (footprint "eagle-import:DISCRETE_SOT23")
      (libsource (lib "eagle-import") (part "DISCRETE_MOSFET-NSOT23"))
    )
    (comp (ref "Q14")
      (value "2N7002")
      (footprint "eagle-import:DISCRETE_SOT23")
      (libsource (lib "eagle-import") (part "DISCRETE_MOSFET-NSOT23"))
    )
    (comp (ref "Q15")
      (value "2N7002")
      (footprint "eagle-import:DISCRETE_SOT23")
      (libsource (lib "eagle-import") (part "DISCRETE_MOSFET-NSOT23"))
    )
    (comp (ref "Q16")
      (value "2N7002")
      (footprint "eagle-import:DISCRETE_SOT23")
      (libsource (lib "eagle-import") (part "DISCRETE_MOSFET-NSOT23"))
    )
    (comp (ref "Q17")
      (value "2N7002")
      (footprint "eagle-import:DISCRETE_SOT23")
      (libsource (lib "eagle-import") (part "DISCRETE_MOSFET-NSOT23"))
    )
    (comp (ref "Q18")
      (value "2N7002")
      (footprint "eagle-import:DISCRETE_SOT23")
      (libsource (lib "eagle-import") (part "DISCRETE_MOSFET-NSOT23"))
    )
    (comp (ref "Q24")
      (value "2N7002")
      (footprint "eagle-import:DISCRETE_SOT23")
      (libsource (lib "eagle-import") (part "DISCRETE_MOSFET-NSOT23"))
    )
    (comp (ref "Q25")
      (value "2N7002")
      (footprint "eagle-import:DISCRETE_SOT23")
      (libsource (lib "eagle-import") (part "DISCRETE_MOSFET-NSOT23"))
    )
    (comp (ref "Q26")
      (value "2N7002")
      (footprint "eagle-import:DISCRETE_SOT23")
      (libsource (lib "eagle-import") (part "DISCRETE_MOSFET-NSOT23"))
    )
    (comp (ref "Q27")
      (value "2N7002")
      (footprint "eagle-import:DISCRETE_SOT23")
      (libsource (lib "eagle-import") (part "DISCRETE_MOSFET-NSOT23"))
    )
    (comp (ref "Q28")
      (value "2N7002")
      (footprint "eagle-import:DISCRETE_SOT23")
      (libsource (lib "eagle-import") (part "DISCRETE_MOSFET-NSOT23"))
    )
    (comp (ref "Q29")
      (value "2N7002")
      (footprint "eagle-import:DISCRETE_SOT23")
      (libsource (lib "eagle-import") (part "DISCRETE_MOSFET-NSOT23"))
    )
    (comp (ref "Q30")
      (value "2N7002")
      (footprint "eagle-import:DISCRETE_SOT23")
      (libsource (lib "eagle-import") (part "DISCRETE_MOSFET-NSOT23"))
    )
    (comp (ref "Q31")
      (value "2N7002")
      (footprint "eagle-import:DISCRETE_SOT23")
      (libsource (lib "eagle-import") (part "DISCRETE_MOSFET-NSOT23"))
    )
    (comp (ref "R1")
      (value "10K")
      (footprint "eagle-import:DISCRETE_R0603")
      (libsource (lib "eagle-import") (part "DISCRETE_R-0603"))
    )
    (comp (ref "R2")
      (value "1K")
      (footprint "eagle-import:DISCRETE_R0603")
      (libsource (lib "eagle-import") (part "DISCRETE_R-0603"))
    )
    (comp (ref "R3")
      (value "4.7K")
      (footprint "eagle-import:DISCRETE_R0603")
      (libsource (lib "eagle-import") (part "DISCRETE_R-0603"))
    )
    (comp (ref "R4")
      (value "4.7K")
      (footprint "eagle-import:DISCRETE_R0603")
      (libsource (lib "eagle-import") (part "DISCRETE_R-0603"))
    )
    (comp (ref "R5")
      (value "0R")
      (footprint "eagle-import:DISCRETE_R0603")
      (libsource (lib "eagle-import") (part "DISCRETE_R-0603"))
    )
    (comp (ref "R6")
      (value "1K")
      (footprint "eagle-import:DISCRETE_R0603")
      (libsource (lib "eagle-import") (part "DISCRETE_R-0603"))
    )
    (comp (ref "R7")
      (value "10K")
      (footprint "eagle-import:DISCRETE_R0603")
      (libsource (lib "eagle-import") (part "DISCRETE_R-0603"))
    )
    (comp (ref "R8")
      (value "4.7K")
      (footprint "eagle-import:DISCRETE_R0603")
      (libsource (lib "eagle-import") (part "DISCRETE_R-0603"))
    )
    (comp (ref "R9")
      (value "4.7K")
      (footprint "eagle-import:DISCRETE_R0603")
      (libsource (lib "eagle-import") (part "DISCRETE_R-0603"))
    )
    (comp (ref "R10")
      (value "22R")
      (footprint "eagle-import:DISCRETE_R0603")
      (libsource (lib "eagle-import") (part "DISCRETE_R-0603"))
    )
    (comp (ref "R11")
      (value "22R")
      (footprint "eagle-import:DISCRETE_R0603")
      (libsource (lib "eagle-import") (part "DISCRETE_R-0603"))
    )
    (comp (ref "R12")
      (value "5.1K")
      (footprint "eagle-import:DISCRETE_R0603")
      (libsource (lib "eagle-import") (part "DISCRETE_R-0603"))
    )
    (comp (ref "R13")
      (value "5.1K")
      (footprint "eagle-import:DISCRETE_R0603")
      (libsource (lib "eagle-import") (part "DISCRETE_R-0603"))
    )
    (comp (ref "R14")
      (value "4.7K")
      (footprint "eagle-import:DISCRETE_R0603")
      (libsource (lib "eagle-import") (part "DISCRETE_R-0603"))
    )
    (comp (ref "R15")
      (value "10K")
      (footprint "eagle-import:DISCRETE_R0603")
      (libsource (lib "eagle-import") (part "DISCRETE_R-0603"))
    )
    (comp (ref "R16")
      (value "0R")
      (footprint "eagle-import:DISCRETE_R0603")
      (libsource (lib "eagle-import") (part "DISCRETE_R-0603"))
    )
    (comp (ref "R17")
      (value "0R")
      (footprint "eagle-import:DISCRETE_R0603")
      (libsource (lib "eagle-import") (part "DISCRETE_R-0603"))
    )
    (comp (ref "R18")
      (value "0R")
      (footprint "eagle-import:DISCRETE_R0603")
      (libsource (lib "eagle-import") (part "DISCRETE_R-0603"))
    )
    (comp (ref "R19")
      (value "1K")
      (footprint "eagle-import:DISCRETE_R0603")
      (libsource (lib "eagle-import") (part "DISCRETE_R-0603"))
    )
    (comp (ref "R20")
      (value "4.7K")
      (footprint "eagle-import:DISCRETE_R0603")
      (libsource (lib "eagle-import") (part "DISCRETE_R-0603"))
    )
    (comp (ref "R21")
      (value "22R")
      (footprint "eagle-import:DISCRETE_R0603")
      (libsource (lib "eagle-import") (part "DISCRETE_R-0603"))
    )
    (comp (ref "R22")
      (value "10K")
      (footprint "eagle-import:DISCRETE_R0603")
      (libsource (lib "eagle-import") (part "DISCRETE_R-0603"))
    )
    (comp (ref "R23")
      (value "1K")
      (footprint "eagle-import:DISCRETE_R0603")
      (libsource (lib "eagle-import") (part "DISCRETE_R-0603"))
    )
    (comp (ref "R24")
      (value "1K")
      (footprint "eagle-import:DISCRETE_R0603")
      (libsource (lib "eagle-import") (part "DISCRETE_R-0603"))
    )
    (comp (ref "R25")
      (value "1K")
      (footprint "eagle-import:DISCRETE_R0603")
      (libsource (lib "eagle-import") (part "DISCRETE_R-0603"))
    )
    (comp (ref "R26")
      (value "1K")
      (footprint "eagle-import:DISCRETE_R0603")
      (libsource (lib "eagle-import") (part "DISCRETE_R-0603"))
    )
    (comp (ref "R27")
      (value "100R")
      (footprint "eagle-import:DISCRETE_R0603")
      (libsource (lib "eagle-import") (part "DISCRETE_R-0603"))
    )
    (comp (ref "R28")
      (value "1K")
      (footprint "eagle-import:DISCRETE_R0603")
      (libsource (lib "eagle-import") (part "DISCRETE_R-0603"))
    )
    (comp (ref "R29")
      (value "10K")
      (footprint "eagle-import:DISCRETE_R0603")
      (libsource (lib "eagle-import") (part "DISCRETE_R-0603"))
    )
    (comp (ref "R30")
      (value "4.7K")
      (footprint "eagle-import:DISCRETE_R0603")
      (libsource (lib "eagle-import") (part "DISCRETE_R-0603"))
    )
    (comp (ref "R31")
      (value "4.7K")
      (footprint "eagle-import:DISCRETE_R0603")
      (libsource (lib "eagle-import") (part "DISCRETE_R-0603"))
    )
    (comp (ref "R32")
      (value "4.7K")
      (footprint "eagle-import:DISCRETE_R0603")
      (libsource (lib "eagle-import") (part "DISCRETE_R-0603"))
    )
    (comp (ref "R33")
      (value "240R 1%")
      (footprint "eagle-import:DISCRETE_R0603")
      (libsource (lib "eagle-import") (part "DISCRETE_R-0603"))
    )
    (comp (ref "R34")
      (value "3K")
      (footprint "eagle-import:DISCRETE_R0603")
      (libsource (lib "eagle-import") (part "DISCRETE_R-0603"))
    )
    (comp (ref "R35")
      (value "4.7K")
      (footprint "eagle-import:DISCRETE_R0603")
      (libsource (lib "eagle-import") (part "DISCRETE_R-0603"))
    )
    (comp (ref "R36")
      (value "4.7K")
      (footprint "eagle-import:DISCRETE_R0603")
      (libsource (lib "eagle-import") (part "DISCRETE_R-0603"))
    )
    (comp (ref "R37")
      (value "4.7K")
      (footprint "eagle-import:DISCRETE_R0603")
      (libsource (lib "eagle-import") (part "DISCRETE_R-0603"))
    )
    (comp (ref "R38")
      (value "4.7K")
      (footprint "eagle-import:DISCRETE_R0603")
      (libsource (lib "eagle-import") (part "DISCRETE_R-0603"))
    )
    (comp (ref "R39")
      (value "4.7K")
      (footprint "eagle-import:DISCRETE_R0603")
      (libsource (lib "eagle-import") (part "DISCRETE_R-0603"))
    )
    (comp (ref "R40")
      (value "4.7K")
      (footprint "eagle-import:DISCRETE_R0603")
      (libsource (lib "eagle-import") (part "DISCRETE_R-0603"))
    )
    (comp (ref "R41")
      (value "4.7K")
      (footprint "eagle-import:DISCRETE_R0603")
      (libsource (lib "eagle-import") (part "DISCRETE_R-0603"))
    )
    (comp (ref "R42")
      (value "4.7K")
      (footprint "eagle-import:DISCRETE_R0603")
      (libsource (lib "eagle-import") (part "DISCRETE_R-0603"))
    )
    (comp (ref "R43")
      (value "4.7K")
      (footprint "eagle-import:DISCRETE_R0603")
      (libsource (lib "eagle-import") (part "DISCRETE_R-0603"))
    )
    (comp (ref "R44")
      (value "4.7K")
      (footprint "eagle-import:DISCRETE_R0603")
      (libsource (lib "eagle-import") (part "DISCRETE_R-0603"))
    )
    (comp (ref "R45")
      (value "470R 1%")
      (footprint "eagle-import:DISCRETE_R0603")
      (libsource (lib "eagle-import") (part "DISCRETE_R-0603"))
    )
    (comp (ref "R46")
      (value "4.7K")
      (footprint "eagle-import:DISCRETE_R0603")
      (libsource (lib "eagle-import") (part "DISCRETE_R-0603"))
    )
    (comp (ref "R47")
      (value "4.7K")
      (footprint "eagle-import:DISCRETE_R0603")
      (libsource (lib "eagle-import") (part "DISCRETE_R-0603"))
    )
    (comp (ref "R48")
      (value "4.7K")
      (footprint "eagle-import:DISCRETE_R0603")
      (libsource (lib "eagle-import") (part "DISCRETE_R-0603"))
    )
    (comp (ref "R49")
      (value "4.7K")
      (footprint "eagle-import:DISCRETE_R0603")
      (libsource (lib "eagle-import") (part "DISCRETE_R-0603"))
    )
    (comp (ref "R50")
      (value "4.7K")
      (footprint "eagle-import:DISCRETE_R0603")
      (libsource (lib "eagle-import") (part "DISCRETE_R-0603"))
    )
    (comp (ref "R51")
      (value "4.7K")
      (footprint "eagle-import:DISCRETE_R0603")
      (libsource (lib "eagle-import") (part "DISCRETE_R-0603"))
    )
    (comp (ref "R52")
      (value "4.7K")
      (footprint "eagle-import:DISCRETE_R0603")
      (libsource (lib "eagle-import") (part "DISCRETE_R-0603"))
    )
    (comp (ref "R53")
      (value "4.7K")
      (footprint "eagle-import:DISCRETE_R0603")
      (libsource (lib "eagle-import") (part "DISCRETE_R-0603"))
    )
    (comp (ref "R54")
      (value "4.7K")
      (footprint "eagle-import:DISCRETE_R0603")
      (libsource (lib "eagle-import") (part "DISCRETE_R-0603"))
    )
    (comp (ref "R55")
      (value "4.7K")
      (footprint "eagle-import:DISCRETE_R0603")
      (libsource (lib "eagle-import") (part "DISCRETE_R-0603"))
    )
    (comp (ref "R56")
      (value "4.7K")
      (footprint "eagle-import:DISCRETE_R0603")
      (libsource (lib "eagle-import") (part "DISCRETE_R-0603"))
    )
    (comp (ref "R57")
      (value "4.7K")
      (footprint "eagle-import:DISCRETE_R0603")
      (libsource (lib "eagle-import") (part "DISCRETE_R-0603"))
    )
    (comp (ref "R58")
      (value "4.7K")
      (footprint "eagle-import:DISCRETE_R0603")
      (libsource (lib "eagle-import") (part "DISCRETE_R-0603"))
    )
    (comp (ref "R59")
      (value "4.7K")
      (footprint "eagle-import:DISCRETE_R0603")
      (libsource (lib "eagle-import") (part "DISCRETE_R-0603"))
    )
    (comp (ref "R60")
      (value "4.7K")
      (footprint "eagle-import:DISCRETE_R0603")
      (libsource (lib "eagle-import") (part "DISCRETE_R-0603"))
    )
    (comp (ref "R61")
      (value "4.7K")
      (footprint "eagle-import:DISCRETE_R0603")
      (libsource (lib "eagle-import") (part "DISCRETE_R-0603"))
    )
    (comp (ref "R62")
      (value "4.7K")
      (footprint "eagle-import:DISCRETE_R0603")
      (libsource (lib "eagle-import") (part "DISCRETE_R-0603"))
    )
    (comp (ref "R63")
      (value "4.7K")
      (footprint "eagle-import:DISCRETE_R0603")
      (libsource (lib "eagle-import") (part "DISCRETE_R-0603"))
    )
    (comp (ref "R64")
      (value "240R 1%")
      (footprint "eagle-import:DISCRETE_R0603")
      (libsource (lib "eagle-import") (part "DISCRETE_R-0603"))
    )
    (comp (ref "R65")
      (value "470R 1%")
      (footprint "eagle-import:DISCRETE_R0603")
      (libsource (lib "eagle-import") (part "DISCRETE_R-0603"))
    )
    (comp (ref "R71")
      (value "4.7K")
      (footprint "eagle-import:DISCRETE_R0603")
      (libsource (lib "eagle-import") (part "DISCRETE_R-0603"))
    )
    (comp (ref "R72")
      (value "120R")
      (footprint "eagle-import:DISCRETE_R0603")
      (libsource (lib "eagle-import") (part "DISCRETE_R-0603"))
    )
    (comp (ref "R73")
      (value "4.7K")
      (footprint "eagle-import:DISCRETE_R0603")
      (libsource (lib "eagle-import") (part "DISCRETE_R-0603"))
    )
    (comp (ref "R74")
      (value "4.7K")
      (footprint "eagle-import:DISCRETE_R0603")
      (libsource (lib "eagle-import") (part "DISCRETE_R-0603"))
    )
    (comp (ref "R75")
      (value "1K")
      (footprint "eagle-import:DISCRETE_R0603")
      (libsource (lib "eagle-import") (part "DISCRETE_R-0603"))
    )
    (comp (ref "R76")
      (value "1K")
      (footprint "eagle-import:DISCRETE_R0603")
      (libsource (lib "eagle-import") (part "DISCRETE_R-0603"))
    )
    (comp (ref "R77")
      (value "1K")
      (footprint "eagle-import:DISCRETE_R0603")
      (libsource (lib "eagle-import") (part "DISCRETE_R-0603"))
    )
    (comp (ref "R78")
      (value "1K")
      (footprint "eagle-import:DISCRETE_R0603")
      (libsource (lib "eagle-import") (part "DISCRETE_R-0603"))
    )
    (comp (ref "R79")
      (value "1K")
      (footprint "eagle-import:DISCRETE_R0603")
      (libsource (lib "eagle-import") (part "DISCRETE_R-0603"))
    )
    (comp (ref "R80")
      (value "1K")
      (footprint "eagle-import:DISCRETE_R0603")
      (libsource (lib "eagle-import") (part "DISCRETE_R-0603"))
    )
    (comp (ref "R81")
      (value "45.3K 1%")
      (footprint "eagle-import:DISCRETE_R0603")
      (libsource (lib "eagle-import") (part "DISCRETE_R-0603"))
    )
    (comp (ref "R82")
      (value "10K 1%")
      (footprint "eagle-import:DISCRETE_R0603")
      (libsource (lib "eagle-import") (part "DISCRETE_R-0603"))
    )
    (comp (ref "R87")
      (value "4.7K")
      (footprint "eagle-import:DISCRETE_R0603")
      (libsource (lib "eagle-import") (part "DISCRETE_R-0603"))
    )
    (comp (ref "R88")
      (value "4.7K")
      (footprint "eagle-import:DISCRETE_R0603")
      (libsource (lib "eagle-import") (part "DISCRETE_R-0603"))
    )
    (comp (ref "R89")
      (value "4.7K")
      (footprint "eagle-import:DISCRETE_R0603")
      (libsource (lib "eagle-import") (part "DISCRETE_R-0603"))
    )
    (comp (ref "R90")
      (value "4.7K")
      (footprint "eagle-import:DISCRETE_R0603")
      (libsource (lib "eagle-import") (part "DISCRETE_R-0603"))
    )
    (comp (ref "R91")
      (value "4.7K")
      (footprint "eagle-import:DISCRETE_R0603")
      (libsource (lib "eagle-import") (part "DISCRETE_R-0603"))
    )
    (comp (ref "R92")
      (value "4.7K")
      (footprint "eagle-import:DISCRETE_R0603")
      (libsource (lib "eagle-import") (part "DISCRETE_R-0603"))
    )
    (comp (ref "R93")
      (value "4.7K")
      (footprint "eagle-import:DISCRETE_R0603")
      (libsource (lib "eagle-import") (part "DISCRETE_R-0603"))
    )
    (comp (ref "R94")
      (value "4.7K")
      (footprint "eagle-import:DISCRETE_R0603")
      (libsource (lib "eagle-import") (part "DISCRETE_R-0603"))
    )
    (comp (ref "R95")
      (value "4.7K")
      (footprint "eagle-import:DISCRETE_R0603")
      (libsource (lib "eagle-import") (part "DISCRETE_R-0603"))
    )
    (comp (ref "R96")
      (value "4.7K")
      (footprint "eagle-import:DISCRETE_R0603")
      (libsource (lib "eagle-import") (part "DISCRETE_R-0603"))
    )
    (comp (ref "R97")
      (value "4.7K")
      (footprint "eagle-import:DISCRETE_R0603")
      (libsource (lib "eagle-import") (part "DISCRETE_R-0603"))
    )
    (comp (ref "R98")
      (value "4.7K")
      (footprint "eagle-import:DISCRETE_R0603")
      (libsource (lib "eagle-import") (part "DISCRETE_R-0603"))
    )
    (comp (ref "R99")
      (value "4.7K")
      (footprint "eagle-import:DISCRETE_R0603")
      (libsource (lib "eagle-import") (part "DISCRETE_R-0603"))
    )
    (comp (ref "R100")
      (value "4.7K")
      (footprint "eagle-import:DISCRETE_R0603")
      (libsource (lib "eagle-import") (part "DISCRETE_R-0603"))
    )
    (comp (ref "R101")
      (value "4.7K")
      (footprint "eagle-import:DISCRETE_R0603")
      (libsource (lib "eagle-import") (part "DISCRETE_R-0603"))
    )
    (comp (ref "R102")
      (value "4.7K")
      (footprint "eagle-import:DISCRETE_R0603")
      (libsource (lib "eagle-import") (part "DISCRETE_R-0603"))
    )
    (comp (ref "SW1")
      (value "MYSMD_PB157_4.3X3")
      (footprint "eagle-import:MYSMD_157SW")
      (libsource (lib "eagle-import") (part "MYSMD_PB157_4.3X3"))
    )
    (comp (ref "SW2")
      (value "MYSMD_PB157_4.3X3")
      (footprint "eagle-import:MYSMD_157SW")
      (libsource (lib "eagle-import") (part "MYSMD_PB157_4.3X3"))
    )
    (comp (ref "SW3")
      (value "MYSMD_PB157_4.3X3")
      (footprint "eagle-import:MYSMD_157SW")
      (libsource (lib "eagle-import") (part "MYSMD_PB157_4.3X3"))
    )
    (comp (ref "U1")
      (value "RP2040_RP2040")
      (footprint "eagle-import:RP2040_QFN-56")
      (libsource (lib "eagle-import") (part "RP2040_RP2040"))
    )
    (comp (ref "U2")
      (value "SELF_W25Q128JV")
      (footprint "eagle-import:SELF_SOIC-8-208MIL")
      (libsource (lib "eagle-import") (part "SELF_W25Q128JV"))
    )
    (comp (ref "U3")
      (value "LD1117-3V3-SOT223")
      (footprint "eagle-import:SOT223")
      (libsource (lib "eagle-import") (part "LD1117-3V3-SOT223"))
    )
    (comp (ref "U4")
      (value "RA08H_MODULE_SMD_18P")
      (footprint "eagle-import:RA08H_MODULE_SMT_18P")
      (libsource (lib "eagle-import") (part "RA08H_MODULE_SMD_18P"))
    )
    (comp (ref "U5")
      (value "MAX3485CSA")
      (footprint "eagle-import:SO08")
      (libsource (lib "eagle-import") (part "RS485SOIC"))
    )
    (comp (ref "U6")
      (value "HM3416H")
      (footprint "eagle-import:CROWBOT_-V1.0-20220525_A_XBJ_SOT23-5")
      (libsource (lib "eagle-import") (part "CROWBOT_-V1.0-20220525_A_XBJ_HM3420B"))
    )
    (comp (ref "X1")
      (value "12MHZ_SMD3225")
      (footprint "eagle-import:A_XBJ_SMD3225")
      (libsource (lib "eagle-import") (part "A_XBJ_XTAL"))
    )
  )
  (nets
    (net (code "1") (name "+1V1") (class "Default")
      (node (ref "C13") (pin "1") (pinfunction "1_1") (pintype "passive"))
      (node (ref "C14") (pin "1") (pinfunction "1_1") (pintype "passive"))
      (node (ref "C16") (pin "1") (pinfunction "1_1") (pintype "passive"))
      (node (ref "U1") (pin "23") (pinfunction "VDD_1V1_23") (pintype "bidirectional"))
      (node (ref "U1") (pin "45") (pinfunction "LDO_OUT_45") (pintype "bidirectional"))
      (node (ref "U1") (pin "50") (pinfunction "VDD_1V1_50") (pintype "bidirectional"))
    )
    (net (code "2") (name "+3V3") (class "Default")
      (node (ref "C10") (pin "1") (pinfunction "1_1") (pintype "passive"))
      (node (ref "C11") (pin "1") (pinfunction "1_1") (pintype "passive"))
      (node (ref "C12") (pin "1") (pinfunction "1_1") (pintype "passive"))
      (node (ref "C15") (pin "1") (pinfunction "1_1") (pintype "passive"))
      (node (ref "C24") (pin "1") (pinfunction "1_1") (pintype "passive"))
      (node (ref "C25") (pin "1") (pinfunction "1_1") (pintype "passive"))
      (node (ref "C26") (pin "2") (pinfunction "2_2") (pintype "passive"))
      (node (ref "C33") (pin "2") (pinfunction "2_2") (pintype "passive"))
      (node (ref "C34") (pin "1") (pinfunction "1_1") (pintype "passive"))
      (node (ref "C35") (pin "1") (pinfunction "1_1") (pintype "passive"))
      (node (ref "C36") (pin "1") (pinfunction "1_1") (pintype "passive"))
      (node (ref "C5") (pin "1") (pinfunction "1_1") (pintype "passive"))
      (node (ref "C6") (pin "1") (pinfunction "1_1") (pintype "passive"))
      (node (ref "C7") (pin "1") (pinfunction "1_1") (pintype "passive"))
      (node (ref "C8") (pin "1") (pinfunction "1_1") (pintype "passive"))
      (node (ref "C9") (pin "1") (pinfunction "1_1") (pintype "passive"))
      (node (ref "IC1") (pin "16") (pinfunction "VCC_16") (pintype "bidirectional"))
      (node (ref "J26") (pin "1") (pinfunction "1_1") (pintype "passive"))
      (node (ref "J26") (pin "10") (pinfunction "10_10") (pintype "passive"))
      (node (ref "J26") (pin "11") (pinfunction "11_11") (pintype "passive"))
      (node (ref "J26") (pin "12") (pinfunction "12_12") (pintype "passive"))
      (node (ref "J26") (pin "13") (pinfunction "13_13") (pintype "passive"))
      (node (ref "J26") (pin "14") (pinfunction "14_14") (pintype "passive"))
      (node (ref "J26") (pin "2") (pinfunction "2_2") (pintype "passive"))
      (node (ref "J26") (pin "3") (pinfunction "3_3") (pintype "passive"))
      (node (ref "J26") (pin "4") (pinfunction "4_4") (pintype "passive"))
      (node (ref "J26") (pin "5") (pinfunction "5_5") (pintype "passive"))
      (node (ref "J26") (pin "6") (pinfunction "6_6") (pintype "passive"))
      (node (ref "J26") (pin "7") (pinfunction "7_7") (pintype "passive"))
      (node (ref "J26") (pin "8") (pinfunction "8_8") (pintype "passive"))
      (node (ref "J26") (pin "9") (pinfunction "9_9") (pintype "passive"))
      (node (ref "J48") (pin "1") (pinfunction "1_1") (pintype "passive"))
      (node (ref "L1") (pin "2") (pinfunction "2_2") (pintype "passive"))
      (node (ref "LCD1") (pin "10") (pinfunction "VCC_10") (pintype "power_in"))
      (node (ref "LCD1") (pin "11") (pinfunction "IOVCC_11") (pintype "bidirectional"))
      (node (ref "LCD1") (pin "4") (pinfunction "LED+_4") (pintype "bidirectional"))
      (node (ref "P13") (pin "P$1") (pinfunction "P$1_P$1") (pintype "bidirectional"))
      (node (ref "Q1") (pin "1") (pinfunction "G_1") (pintype "passive"))
      (node (ref "Q10") (pin "1") (pinfunction "G_1") (pintype "passive"))
      (node (ref "Q11") (pin "1") (pinfunction "G_1") (pintype "passive"))
      (node (ref "Q12") (pin "1") (pinfunction "G_1") (pintype "passive"))
      (node (ref "Q13") (pin "1") (pinfunction "G_1") (pintype "passive"))
      (node (ref "Q14") (pin "1") (pinfunction "G_1") (pintype "passive"))
      (node (ref "Q15") (pin "1") (pinfunction "G_1") (pintype "passive"))
      (node (ref "Q16") (pin "1") (pinfunction "G_1") (pintype "passive"))
      (node (ref "Q17") (pin "1") (pinfunction "G_1") (pintype "passive"))
      (node (ref "Q18") (pin "1") (pinfunction "G_1") (pintype "passive"))
      (node (ref "Q2") (pin "1") (pinfunction "G_1") (pintype "passive"))
      (node (ref "Q24") (pin "1") (pinfunction "G_1") (pintype "passive"))
      (node (ref "Q25") (pin "1") (pinfunction "G_1") (pintype "passive"))
      (node (ref "Q26") (pin "1") (pinfunction "G_1") (pintype "passive"))
      (node (ref "Q27") (pin "1") (pinfunction "G_1") (pintype "passive"))
      (node (ref "Q28") (pin "1") (pinfunction "G_1") (pintype "passive"))
      (node (ref "Q29") (pin "1") (pinfunction "G_1") (pintype "passive"))
      (node (ref "Q30") (pin "1") (pinfunction "G_1") (pintype "passive"))
      (node (ref "Q31") (pin "1") (pinfunction "G_1") (pintype "passive"))
      (node (ref "Q5") (pin "1") (pinfunction "G_1") (pintype "passive"))
      (node (ref "Q6") (pin "1") (pinfunction "G_1") (pintype "passive"))
      (node (ref "Q7") (pin "1") (pinfunction "G_1") (pintype "passive"))
      (node (ref "Q8") (pin "1") (pinfunction "G_1") (pintype "passive"))
      (node (ref "Q9") (pin "1") (pinfunction "G_1") (pintype "passive"))
      (node (ref "R1") (pin "2") (pinfunction "2_2") (pintype "passive"))
      (node (ref "R101") (pin "2") (pinfunction "2_2") (pintype "passive"))
      (node (ref "R14") (pin "2") (pinfunction "2_2") (pintype "passive"))
      (node (ref "R20") (pin "2") (pinfunction "2_2") (pintype "passive"))
      (node (ref "R23") (pin "2") (pinfunction "2_2") (pintype "passive"))
      (node (ref "R27") (pin "2") (pinfunction "2_2") (pintype "passive"))
      (node (ref "R3") (pin "2") (pinfunction "2_2") (pintype "passive"))
      (node (ref "R31") (pin "2") (pinfunction "2_2") (pintype "passive"))
      (node (ref "R35") (pin "2") (pinfunction "2_2") (pintype "passive"))
      (node (ref "R36") (pin "2") (pinfunction "2_2") (pintype "passive"))
      (node (ref "R38") (pin "2") (pinfunction "2_2") (pintype "passive"))
      (node (ref "R40") (pin "2") (pinfunction "2_2") (pintype "passive"))
      (node (ref "R42") (pin "2") (pinfunction "2_2") (pintype "passive"))
      (node (ref "R43") (pin "2") (pinfunction "2_2") (pintype "passive"))
      (node (ref "R44") (pin "2") (pinfunction "2_2") (pintype "passive"))
      (node (ref "R46") (pin "2") (pinfunction "2_2") (pintype "passive"))
      (node (ref "R48") (pin "2") (pinfunction "2_2") (pintype "passive"))
      (node (ref "R5") (pin "2") (pinfunction "2_2") (pintype "passive"))
      (node (ref "R50") (pin "2") (pinfunction "2_2") (pintype "passive"))
      (node (ref "R52") (pin "2") (pinfunction "2_2") (pintype "passive"))
      (node (ref "R54") (pin "2") (pinfunction "2_2") (pintype "passive"))
      (node (ref "R56") (pin "2") (pinfunction "2_2") (pintype "passive"))
      (node (ref "R58") (pin "2") (pinfunction "2_2") (pintype "passive"))
      (node (ref "R60") (pin "2") (pinfunction "2_2") (pintype "passive"))
      (node (ref "R62") (pin "2") (pinfunction "2_2") (pintype "passive"))
      (node (ref "R7") (pin "2") (pinfunction "2_2") (pintype "passive"))
      (node (ref "R71") (pin "2") (pinfunction "2_2") (pintype "passive"))
      (node (ref "R74") (pin "1") (pinfunction "1_1") (pintype "passive"))
      (node (ref "R75") (pin "2") (pinfunction "2_2") (pintype "passive"))
      (node (ref "R76") (pin "2") (pinfunction "2_2") (pintype "passive"))
      (node (ref "R77") (pin "2") (pinfunction "2_2") (pintype "passive"))
      (node (ref "R78") (pin "2") (pinfunction "2_2") (pintype "passive"))
      (node (ref "R79") (pin "2") (pinfunction "2_2") (pintype "passive"))
      (node (ref "R8") (pin "2") (pinfunction "2_2") (pintype "passive"))
      (node (ref "R80") (pin "2") (pinfunction "2_2") (pintype "passive"))
      (node (ref "R81") (pin "1") (pinfunction "1_1") (pintype "passive"))
      (node (ref "R87") (pin "2") (pinfunction "2_2") (pintype "passive"))
      (node (ref "R89") (pin "2") (pinfunction "2_2") (pintype "passive"))
      (node (ref "R91") (pin "2") (pinfunction "2_2") (pintype "passive"))
      (node (ref "R93") (pin "2") (pinfunction "2_2") (pintype "passive"))
      (node (ref "R95") (pin "2") (pinfunction "2_2") (pintype "passive"))
      (node (ref "R97") (pin "2") (pinfunction "2_2") (pintype "passive"))
      (node (ref "R99") (pin "2") (pinfunction "2_2") (pintype "passive"))
      (node (ref "U1") (pin "1") (pinfunction "VDDIO_1") (pintype "bidirectional"))
      (node (ref "U1") (pin "10") (pinfunction "VDDIO_10") (pintype "bidirectional"))
      (node (ref "U1") (pin "22") (pinfunction "VDDIO_22") (pintype "bidirectional"))
      (node (ref "U1") (pin "33") (pinfunction "VDDIO_33") (pintype "bidirectional"))
      (node (ref "U1") (pin "42") (pinfunction "VDDIO_42") (pintype "bidirectional"))
      (node (ref "U1") (pin "44") (pinfunction "LDO_IN_44") (pintype "bidirectional"))
      (node (ref "U1") (pin "48") (pinfunction "USB_VDD_48") (pintype "bidirectional"))
      (node (ref "U1") (pin "49") (pinfunction "VDDIO_49") (pintype "bidirectional"))
      (node (ref "U2") (pin "8") (pinfunction "VCC_8") (pintype "bidirectional"))
      (node (ref "U5") (pin "8") (pinfunction "VCC_8") (pintype "bidirectional"))
    )
    (net (code "3") (name "+5V") (class "Default")
      (node (ref "C31") (pin "2") (pinfunction "2_2") (pintype "passive"))
      (node (ref "C32") (pin "1") (pinfunction "1_1") (pintype "passive"))
      (node (ref "D11") (pin "+") (pinfunction "+_+") (pintype "passive"))
      (node (ref "J1") (pin "2") (pinfunction "2_2") (pintype "bidirectional"))
      (node (ref "J10") (pin "2") (pinfunction "2_2") (pintype "bidirectional"))
      (node (ref "J11") (pin "2") (pinfunction "2_2") (pintype "bidirectional"))
      (node (ref "J12") (pin "2") (pinfunction "2_2") (pintype "bidirectional"))
      (node (ref "J14") (pin "A4") (pinfunction "A4_A4") (pintype "bidirectional"))
      (node (ref "J14") (pin "A9") (pinfunction "A9_A9") (pintype "bidirectional"))
      (node (ref "J14") (pin "B4") (pinfunction "B4_B4") (pintype "bidirectional"))
      (node (ref "J14") (pin "B9") (pinfunction "B9_B9") (pintype "bidirectional"))
      (node (ref "J19") (pin "1") (pinfunction "1_1") (pintype "passive"))
      (node (ref "J19") (pin "10") (pinfunction "10_10") (pintype "passive"))
      (node (ref "J19") (pin "11") (pinfunction "11_11") (pintype "passive"))
      (node (ref "J19") (pin "12") (pinfunction "12_12") (pintype "passive"))
      (node (ref "J19") (pin "2") (pinfunction "2_2") (pintype "passive"))
      (node (ref "J19") (pin "3") (pinfunction "3_3") (pintype "passive"))
      (node (ref "J19") (pin "4") (pinfunction "4_4") (pintype "passive"))
      (node (ref "J19") (pin "5") (pinfunction "5_5") (pintype "passive"))
      (node (ref "J19") (pin "6") (pinfunction "6_6") (pintype "passive"))
      (node (ref "J19") (pin "7") (pinfunction "7_7") (pintype "passive"))
      (node (ref "J19") (pin "8") (pinfunction "8_8") (pintype "passive"))
      (node (ref "J19") (pin "9") (pinfunction "9_9") (pintype "passive"))
      (node (ref "J48") (pin "3") (pinfunction "3_3") (pintype "passive"))
      (node (ref "J6") (pin "2") (pinfunction "2_2") (pintype "bidirectional"))
      (node (ref "J7") (pin "2") (pinfunction "2_2") (pintype "bidirectional"))
      (node (ref "J8") (pin "2") (pinfunction "2_2") (pintype "bidirectional"))
      (node (ref "J9") (pin "2") (pinfunction "2_2") (pintype "bidirectional"))
      (node (ref "P2") (pin "P$1") (pinfunction "P$1_P$1") (pintype "bidirectional"))
      (node (ref "R30") (pin "2") (pinfunction "2_2") (pintype "passive"))
      (node (ref "R32") (pin "2") (pinfunction "2_2") (pintype "passive"))
      (node (ref "R37") (pin "2") (pinfunction "2_2") (pintype "passive"))
      (node (ref "R39") (pin "2") (pinfunction "2_2") (pintype "passive"))
      (node (ref "R4") (pin "2") (pinfunction "2_2") (pintype "passive"))
      (node (ref "R41") (pin "2") (pinfunction "2_2") (pintype "passive"))
      (node (ref "R47") (pin "2") (pinfunction "2_2") (pintype "passive"))
      (node (ref "R49") (pin "2") (pinfunction "2_2") (pintype "passive"))
      (node (ref "R51") (pin "2") (pinfunction "2_2") (pintype "passive"))
      (node (ref "R53") (pin "2") (pinfunction "2_2") (pintype "passive"))
      (node (ref "R55") (pin "2") (pinfunction "2_2") (pintype "passive"))
      (node (ref "R57") (pin "2") (pinfunction "2_2") (pintype "passive"))
      (node (ref "R59") (pin "2") (pinfunction "2_2") (pintype "passive"))
      (node (ref "R61") (pin "2") (pinfunction "2_2") (pintype "passive"))
      (node (ref "R63") (pin "2") (pinfunction "2_2") (pintype "passive"))
      (node (ref "R9") (pin "2") (pinfunction "2_2") (pintype "passive"))
      (node (ref "U6") (pin "1") (pinfunction "EN_1") (pintype "bidirectional"))
      (node (ref "U6") (pin "4") (pinfunction "VIN_4") (pintype "bidirectional"))
    )
    (net (code "4") (name "+VCC") (class "Default")
      (node (ref "J4") (pin "2") (pinfunction "2_2") (pintype "passive"))
      (node (ref "J46") (pin "2") (pinfunction "2_2") (pintype "passive"))
      (node (ref "J47") (pin "2") (pinfunction "2_2") (pintype "passive"))
      (node (ref "J48") (pin "2") (pinfunction "2_2") (pintype "passive"))
      (node (ref "J49") (pin "2") (pinfunction "2_2") (pintype "passive"))
      (node (ref "J50") (pin "2") (pinfunction "2_2") (pintype "passive"))
      (node (ref "R100") (pin "2") (pinfunction "2_2") (pintype "passive"))
      (node (ref "R102") (pin "2") (pinfunction "2_2") (pintype "passive"))
      (node (ref "R88") (pin "2") (pinfunction "2_2") (pintype "passive"))
      (node (ref "R90") (pin "2") (pinfunction "2_2") (pintype "passive"))
      (node (ref "R92") (pin "2") (pinfunction "2_2") (pintype "passive"))
      (node (ref "R94") (pin "2") (pinfunction "2_2") (pintype "passive"))
      (node (ref "R96") (pin "2") (pinfunction "2_2") (pintype "passive"))
      (node (ref "R98") (pin "2") (pinfunction "2_2") (pintype "passive"))
    )
    (net (code "5") (name "/A+") (class "Default")
      (node (ref "J13") (pin "2") (pinfunction "2_2") (pintype "bidirectional"))
      (node (ref "R72") (pin "1") (pinfunction "1_1") (pintype "passive"))
      (node (ref "R74") (pin "2") (pinfunction "2_2") (pintype "passive"))
      (node (ref "U5") (pin "6") (pinfunction "A_6") (pintype "bidirectional"))
    )
    (net (code "6") (name "/B-") (class "Default")
      (node (ref "J13") (pin "1") (pinfunction "1_1") (pintype "bidirectional"))
      (node (ref "R72") (pin "2") (pinfunction "2_2") (pintype "passive"))
      (node (ref "R73") (pin "1") (pinfunction "1_1") (pintype "passive"))
      (node (ref "U5") (pin "7") (pinfunction "B_7") (pintype "bidirectional"))
    )
    (net (code "7") (name "A0") (class "Default")
      (node (ref "J5") (pin "14") (pinfunction "14_14") (pintype "passive"))
      (node (ref "R64") (pin "1") (pinfunction "1_1") (pintype "passive"))
      (node (ref "R65") (pin "2") (pinfunction "2_2") (pintype "passive"))
      (node (ref "U1") (pin "38") (pinfunction "GPIO26/ADC0_38") (pintype "bidirectional"))
    )
    (net (code "8") (name "A0_IN") (class "Default")
      (node (ref "J8") (pin "4") (pinfunction "4_4") (pintype "bidirectional"))
      (node (ref "R64") (pin "2") (pinfunction "2_2") (pintype "passive"))
    )
    (net (code "9") (name "A1") (class "Default")
      (node (ref "J5") (pin "13") (pinfunction "13_13") (pintype "passive"))
      (node (ref "R33") (pin "1") (pinfunction "1_1") (pintype "passive"))
      (node (ref "R45") (pin "2") (pinfunction "2_2") (pintype "passive"))
      (node (ref "U1") (pin "39") (pinfunction "GPIO27/ADC1_39") (pintype "bidirectional"))
    )
    (net (code "10") (name "A1_IN") (class "Default")
      (node (ref "J7") (pin "4") (pinfunction "4_4") (pintype "bidirectional"))
      (node (ref "R33") (pin "2") (pinfunction "2_2") (pintype "passive"))
    )
    (net (code "11") (name "A2") (class "Default")
      (node (ref "R28") (pin "2") (pinfunction "2_2") (pintype "passive"))
      (node (ref "U1") (pin "40") (pinfunction "GPIO28/ADC2_40") (pintype "bidirectional"))
    )
    (net (code "12") (name "A3") (class "Default")
      (node (ref "K2") (pin "1") (pinfunction "P$1_1") (pintype "bidirectional"))
      (node (ref "R23") (pin "1") (pinfunction "1_1") (pintype "passive"))
      (node (ref "R24") (pin "2") (pinfunction "2_2") (pintype "passive"))
      (node (ref "U1") (pin "41") (pinfunction "GPIO29/ADC3_41") (pintype "bidirectional"))
    )
    (net (code "13") (name "AVDD") (class "Default")
      (node (ref "C3") (pin "1") (pinfunction "1_1") (pintype "passive"))
      (node (ref "R5") (pin "1") (pinfunction "1_1") (pintype "passive"))
      (node (ref "U1") (pin "43") (pinfunction "ADC_VDD_43") (pintype "bidirectional"))
    )
    (net (code "14") (name "BOOT") (class "Default")
      (node (ref "R6") (pin "2") (pinfunction "2_2") (pintype "passive"))
      (node (ref "SW2") (pin "2") (pinfunction "2_2") (pintype "passive"))
    )
    (net (code "15") (name "D+") (class "Default")
      (node (ref "J14") (pin "A6") (pinfunction "A6_A6") (pintype "bidirectional"))
      (node (ref "J14") (pin "B6") (pinfunction "B6_B6") (pintype "bidirectional"))
      (node (ref "R11") (pin "1") (pinfunction "1_1") (pintype "passive"))
    )
    (net (code "16") (name "D-") (class "Default")
      (node (ref "J14") (pin "A7") (pinfunction "A7_A7") (pintype "bidirectional"))
      (node (ref "J14") (pin "B7") (pinfunction "B7_B7") (pintype "bidirectional"))
      (node (ref "R10") (pin "1") (pinfunction "1_1") (pintype "passive"))
    )
    (net (code "17") (name "D2") (class "Default")
      (node (ref "J5") (pin "12") (pinfunction "12_12") (pintype "passive"))
      (node (ref "Q5") (pin "2") (pinfunction "S_2") (pintype "passive"))
      (node (ref "R36") (pin "1") (pinfunction "1_1") (pintype "passive"))
      (node (ref "U1") (pin "4") (pinfunction "GPIO2_4") (pintype "bidirectional"))
    )
    (net (code "18") (name "D2_H") (class "Default")
      (node (ref "J20") (pin "12") (pinfunction "12_12") (pintype "passive"))
      (node (ref "Q5") (pin "3") (pinfunction "D_3") (pintype "passive"))
      (node (ref "R37") (pin "1") (pinfunction "1_1") (pintype "passive"))
    )
    (net (code "19") (name "D3") (class "Default")
      (node (ref "J5") (pin "11") (pinfunction "11_11") (pintype "passive"))
      (node (ref "Q6") (pin "2") (pinfunction "S_2") (pintype "passive"))
      (node (ref "R38") (pin "1") (pinfunction "1_1") (pintype "passive"))
      (node (ref "U1") (pin "5") (pinfunction "GPIO3_5") (pintype "bidirectional"))
    )
    (net (code "20") (name "D3_H") (class "Default")
      (node (ref "J20") (pin "11") (pinfunction "11_11") (pintype "passive"))
      (node (ref "Q6") (pin "3") (pinfunction "D_3") (pintype "passive"))
      (node (ref "R39") (pin "1") (pinfunction "1_1") (pintype "passive"))
    )
    (net (code "21") (name "D4{slash}TX1") (class "Default")
      (node (ref "R17") (pin "2") (pinfunction "2_2") (pintype "passive"))
      (node (ref "U1") (pin "6") (pinfunction "GPIO4_6") (pintype "bidirectional"))
    )
    (net (code "22") (name "D5{slash}RX1") (class "Default")
      (node (ref "R16") (pin "2") (pinfunction "2_2") (pintype "passive"))
      (node (ref "U1") (pin "7") (pinfunction "GPIO5_7") (pintype "bidirectional"))
    )
    (net (code "23") (name "D6{slash}SDA1") (class "Default")
      (node (ref "J5") (pin "10") (pinfunction "10_10") (pintype "passive"))
      (node (ref "Q10") (pin "2") (pinfunction "S_2") (pintype "passive"))
      (node (ref "R46") (pin "1") (pinfunction "1_1") (pintype "passive"))
      (node (ref "U1") (pin "8") (pinfunction "GPIO6_8") (pintype "bidirectional"))
    )
    (net (code "24") (name "D6{slash}SDA1_H") (class "Default")
      (node (ref "J20") (pin "10") (pinfunction "10_10") (pintype "passive"))
      (node (ref "Q10") (pin "3") (pinfunction "D_3") (pintype "passive"))
      (node (ref "R47") (pin "1") (pinfunction "1_1") (pintype "passive"))
    )
    (net (code "25") (name "D7{slash}SCL1") (class "Default")
      (node (ref "J5") (pin "9") (pinfunction "9_9") (pintype "passive"))
      (node (ref "Q15") (pin "2") (pinfunction "S_2") (pintype "passive"))
      (node (ref "R56") (pin "1") (pinfunction "1_1") (pintype "passive"))
      (node (ref "U1") (pin "9") (pinfunction "GPIO7_9") (pintype "bidirectional"))
    )
    (net (code "26") (name "D7{slash}SCL1_H") (class "Default")
      (node (ref "J20") (pin "9") (pinfunction "9_9") (pintype "passive"))
      (node (ref "Q15") (pin "3") (pinfunction "D_3") (pintype "passive"))
      (node (ref "R57") (pin "1") (pinfunction "1_1") (pintype "passive"))
    )
    (net (code "27") (name "D8{slash}TX1") (class "Default")
      (node (ref "J25") (pin "2") (pinfunction "2_2") (pintype "passive"))
      (node (ref "J5") (pin "8") (pinfunction "8_8") (pintype "passive"))
      (node (ref "U1") (pin "11") (pinfunction "GPIO8_11") (pintype "bidirectional"))
    )
    (net (code "28") (name "D8{slash}TX1_C") (class "Default")
      (node (ref "J25") (pin "3") (pinfunction "3_3") (pintype "passive"))
      (node (ref "Q25") (pin "2") (pinfunction "S_2") (pintype "passive"))
      (node (ref "Q7") (pin "2") (pinfunction "S_2") (pintype "passive"))
      (node (ref "R40") (pin "1") (pinfunction "1_1") (pintype "passive"))
      (node (ref "R89") (pin "1") (pinfunction "1_1") (pintype "passive"))
    )
    (net (code "29") (name "D8{slash}TX1_H") (class "Default")
      (node (ref "J10") (pin "3") (pinfunction "3_3") (pintype "bidirectional"))
      (node (ref "J20") (pin "8") (pinfunction "8_8") (pintype "passive"))
      (node (ref "Q7") (pin "3") (pinfunction "D_3") (pintype "passive"))
      (node (ref "R41") (pin "1") (pinfunction "1_1") (pintype "passive"))
    )
    (net (code "30") (name "D8{slash}TX1_P") (class "Default")
      (node (ref "J50") (pin "4") (pinfunction "4_4") (pintype "passive"))
      (node (ref "Q25") (pin "3") (pinfunction "D_3") (pintype "passive"))
      (node (ref "R90") (pin "1") (pinfunction "1_1") (pintype "passive"))
    )
    (net (code "31") (name "D9{slash}RX1") (class "Default")
      (node (ref "J24") (pin "2") (pinfunction "2_2") (pintype "passive"))
      (node (ref "J5") (pin "7") (pinfunction "7_7") (pintype "passive"))
      (node (ref "U1") (pin "12") (pinfunction "GPIO9_12") (pintype "bidirectional"))
    )
    (net (code "32") (name "D9{slash}RX1_C") (class "Default")
      (node (ref "J24") (pin "3") (pinfunction "3_3") (pintype "passive"))
      (node (ref "Q14") (pin "2") (pinfunction "S_2") (pintype "passive"))
      (node (ref "Q28") (pin "2") (pinfunction "S_2") (pintype "passive"))
      (node (ref "R54") (pin "1") (pinfunction "1_1") (pintype "passive"))
      (node (ref "R95") (pin "1") (pinfunction "1_1") (pintype "passive"))
    )
    (net (code "33") (name "D9{slash}RX1_H") (class "Default")
      (node (ref "J10") (pin "4") (pinfunction "4_4") (pintype "bidirectional"))
      (node (ref "J20") (pin "7") (pinfunction "7_7") (pintype "passive"))
      (node (ref "Q14") (pin "3") (pinfunction "D_3") (pintype "passive"))
      (node (ref "R55") (pin "1") (pinfunction "1_1") (pintype "passive"))
    )
    (net (code "34") (name "D9{slash}RX1_P") (class "Default")
      (node (ref "J50") (pin "3") (pinfunction "3_3") (pintype "passive"))
      (node (ref "Q28") (pin "3") (pinfunction "D_3") (pintype "passive"))
      (node (ref "R96") (pin "1") (pinfunction "1_1") (pintype "passive"))
    )
    (net (code "35") (name "D10{slash}SCK") (class "Default")
      (node (ref "J5") (pin "6") (pinfunction "6_6") (pintype "passive"))
      (node (ref "Q11") (pin "2") (pinfunction "S_2") (pintype "passive"))
      (node (ref "Q30") (pin "2") (pinfunction "S_2") (pintype "passive"))
      (node (ref "R48") (pin "1") (pinfunction "1_1") (pintype "passive"))
      (node (ref "R99") (pin "1") (pinfunction "1_1") (pintype "passive"))
      (node (ref "U1") (pin "13") (pinfunction "GPIO10_13") (pintype "bidirectional"))
    )
    (net (code "36") (name "D10{slash}SCK_H") (class "Default")
      (node (ref "J20") (pin "6") (pinfunction "6_6") (pintype "passive"))
      (node (ref "Q11") (pin "3") (pinfunction "D_3") (pintype "passive"))
      (node (ref "R49") (pin "1") (pinfunction "1_1") (pintype "passive"))
    )
    (net (code "37") (name "D10{slash}SCK_P") (class "Default")
      (node (ref "J46") (pin "6") (pinfunction "6_6") (pintype "passive"))
      (node (ref "Q30") (pin "3") (pinfunction "D_3") (pintype "passive"))
      (node (ref "R100") (pin "1") (pinfunction "1_1") (pintype "passive"))
    )
    (net (code "38") (name "D11{slash}MOSI") (class "Default")
      (node (ref "J5") (pin "5") (pinfunction "5_5") (pintype "passive"))
      (node (ref "Q12") (pin "2") (pinfunction "S_2") (pintype "passive"))
      (node (ref "Q31") (pin "2") (pinfunction "S_2") (pintype "passive"))
      (node (ref "R101") (pin "1") (pinfunction "1_1") (pintype "passive"))
      (node (ref "R50") (pin "1") (pinfunction "1_1") (pintype "passive"))
      (node (ref "U1") (pin "14") (pinfunction "GPIO11_14") (pintype "bidirectional"))
    )
    (net (code "39") (name "D11{slash}MOSI_H") (class "Default")
      (node (ref "J20") (pin "5") (pinfunction "5_5") (pintype "passive"))
      (node (ref "Q12") (pin "3") (pinfunction "D_3") (pintype "passive"))
      (node (ref "R51") (pin "1") (pinfunction "1_1") (pintype "passive"))
    )
    (net (code "40") (name "D11{slash}MOSI_P") (class "Default")
      (node (ref "J46") (pin "5") (pinfunction "5_5") (pintype "passive"))
      (node (ref "Q31") (pin "3") (pinfunction "D_3") (pintype "passive"))
      (node (ref "R102") (pin "1") (pinfunction "1_1") (pintype "passive"))
    )
    (net (code "41") (name "D12{slash}MISO") (class "Default")
      (node (ref "J5") (pin "4") (pinfunction "4_4") (pintype "passive"))
      (node (ref "Q13") (pin "2") (pinfunction "S_2") (pintype "passive"))
      (node (ref "Q26") (pin "2") (pinfunction "S_2") (pintype "passive"))
      (node (ref "R52") (pin "1") (pinfunction "1_1") (pintype "passive"))
      (node (ref "R91") (pin "1") (pinfunction "1_1") (pintype "passive"))
      (node (ref "U1") (pin "15") (pinfunction "GPIO12_15") (pintype "bidirectional"))
    )
    (net (code "42") (name "D12{slash}MISO_H") (class "Default")
      (node (ref "J20") (pin "4") (pinfunction "4_4") (pintype "passive"))
      (node (ref "Q13") (pin "3") (pinfunction "D_3") (pintype "passive"))
      (node (ref "R53") (pin "1") (pinfunction "1_1") (pintype "passive"))
    )
    (net (code "43") (name "D12{slash}MISO_P") (class "Default")
      (node (ref "J46") (pin "4") (pinfunction "4_4") (pintype "passive"))
      (node (ref "Q26") (pin "3") (pinfunction "D_3") (pintype "passive"))
      (node (ref "R92") (pin "1") (pinfunction "1_1") (pintype "passive"))
    )
    (net (code "44") (name "D13{slash}CS") (class "Default")
      (node (ref "J5") (pin "3") (pinfunction "3_3") (pintype "passive"))
      (node (ref "Q16") (pin "2") (pinfunction "S_2") (pintype "passive"))
      (node (ref "Q29") (pin "2") (pinfunction "S_2") (pintype "passive"))
      (node (ref "R58") (pin "1") (pinfunction "1_1") (pintype "passive"))
      (node (ref "R97") (pin "1") (pinfunction "1_1") (pintype "passive"))
      (node (ref "U1") (pin "16") (pinfunction "GPIO13_16") (pintype "bidirectional"))
    )
    (net (code "45") (name "D13{slash}CS_H") (class "Default")
      (node (ref "J20") (pin "3") (pinfunction "3_3") (pintype "passive"))
      (node (ref "Q16") (pin "3") (pinfunction "D_3") (pintype "passive"))
      (node (ref "R59") (pin "1") (pinfunction "1_1") (pintype "passive"))
    )
    (net (code "46") (name "D13{slash}CS_P") (class "Default")
      (node (ref "J46") (pin "3") (pinfunction "3_3") (pintype "passive"))
      (node (ref "Q29") (pin "3") (pinfunction "D_3") (pintype "passive"))
      (node (ref "R98") (pin "1") (pinfunction "1_1") (pintype "passive"))
    )
    (net (code "47") (name "D14") (class "Default")
      (node (ref "J5") (pin "2") (pinfunction "2_2") (pintype "passive"))
      (node (ref "Q17") (pin "2") (pinfunction "S_2") (pintype "passive"))
      (node (ref "R60") (pin "1") (pinfunction "1_1") (pintype "passive"))
      (node (ref "U1") (pin "17") (pinfunction "GPIO14_17") (pintype "bidirectional"))
    )
    (net (code "48") (name "D14_H") (class "Default")
      (node (ref "J20") (pin "2") (pinfunction "2_2") (pintype "passive"))
      (node (ref "J6") (pin "4") (pinfunction "4_4") (pintype "bidirectional"))
      (node (ref "Q17") (pin "3") (pinfunction "D_3") (pintype "passive"))
      (node (ref "R61") (pin "1") (pinfunction "1_1") (pintype "passive"))
    )
    (net (code "49") (name "D15") (class "Default")
      (node (ref "J5") (pin "1") (pinfunction "1_1") (pintype "passive"))
      (node (ref "Q18") (pin "2") (pinfunction "S_2") (pintype "passive"))
      (node (ref "R62") (pin "1") (pinfunction "1_1") (pintype "passive"))
      (node (ref "U1") (pin "18") (pinfunction "GPIO15_18") (pintype "bidirectional"))
    )
    (net (code "50") (name "D15_H") (class "Default")
      (node (ref "J1") (pin "4") (pinfunction "4_4") (pintype "bidirectional"))
      (node (ref "J20") (pin "1") (pinfunction "1_1") (pintype "passive"))
      (node (ref "Q18") (pin "3") (pinfunction "D_3") (pintype "passive"))
      (node (ref "R63") (pin "1") (pinfunction "1_1") (pintype "passive"))
    )
    (net (code "51") (name "D20{slash}SDA0") (class "Default")
      (node (ref "IC1") (pin "2") (pinfunction "SDA_2") (pintype "bidirectional"))
      (node (ref "Q1") (pin "2") (pinfunction "S_2") (pintype "passive"))
      (node (ref "Q27") (pin "2") (pinfunction "S_2") (pintype "passive"))
      (node (ref "R3") (pin "1") (pinfunction "1_1") (pintype "passive"))
      (node (ref "R43") (pin "1") (pinfunction "1_1") (pintype "passive"))
      (node (ref "R93") (pin "1") (pinfunction "1_1") (pintype "passive"))
      (node (ref "U1") (pin "31") (pinfunction "GPIO20_31") (pintype "bidirectional"))
    )
    (net (code "52") (name "D20{slash}SDA0_H") (class "Default")
      (node (ref "J11") (pin "3") (pinfunction "3_3") (pintype "bidirectional"))
      (node (ref "J12") (pin "3") (pinfunction "3_3") (pintype "bidirectional"))
      (node (ref "Q1") (pin "3") (pinfunction "D_3") (pintype "passive"))
      (node (ref "R4") (pin "1") (pinfunction "1_1") (pintype "passive"))
    )
    (net (code "53") (name "D20{slash}SDA0_P") (class "Default")
      (node (ref "J4") (pin "3") (pinfunction "3_3") (pintype "passive"))
      (node (ref "J47") (pin "3") (pinfunction "3_3") (pintype "passive"))
      (node (ref "J49") (pin "3") (pinfunction "3_3") (pintype "passive"))
      (node (ref "Q27") (pin "3") (pinfunction "D_3") (pintype "passive"))
      (node (ref "R94") (pin "1") (pinfunction "1_1") (pintype "passive"))
    )
    (net (code "54") (name "D21{slash}SCL0") (class "Default")
      (node (ref "IC1") (pin "1") (pinfunction "SCL_1") (pintype "bidirectional"))
      (node (ref "Q2") (pin "2") (pinfunction "S_2") (pintype "passive"))
      (node (ref "Q24") (pin "2") (pinfunction "S_2") (pintype "passive"))
      (node (ref "R42") (pin "1") (pinfunction "1_1") (pintype "passive"))
      (node (ref "R8") (pin "1") (pinfunction "1_1") (pintype "passive"))
      (node (ref "R87") (pin "1") (pinfunction "1_1") (pintype "passive"))
      (node (ref "U1") (pin "32") (pinfunction "GPIO21_32") (pintype "bidirectional"))
    )
    (net (code "55") (name "D21{slash}SCL0_H") (class "Default")
      (node (ref "J11") (pin "4") (pinfunction "4_4") (pintype "bidirectional"))
      (node (ref "J12") (pin "4") (pinfunction "4_4") (pintype "bidirectional"))
      (node (ref "Q2") (pin "3") (pinfunction "D_3") (pintype "passive"))
      (node (ref "R9") (pin "1") (pinfunction "1_1") (pintype "passive"))
    )
    (net (code "56") (name "D21{slash}SCL0_P") (class "Default")
      (node (ref "J4") (pin "4") (pinfunction "4_4") (pintype "passive"))
      (node (ref "J47") (pin "4") (pinfunction "4_4") (pintype "passive"))
      (node (ref "J49") (pin "4") (pinfunction "4_4") (pintype "passive"))
      (node (ref "Q24") (pin "3") (pinfunction "D_3") (pintype "passive"))
      (node (ref "R88") (pin "1") (pinfunction "1_1") (pintype "passive"))
    )
    (net (code "57") (name "D24") (class "Default")
      (node (ref "U1") (pin "36") (pinfunction "GPIO24_36") (pintype "bidirectional"))
      (node (ref "U5") (pin "2") (pinfunction "/RE_2") (pintype "bidirectional"))
      (node (ref "U5") (pin "3") (pinfunction "DE_3") (pintype "bidirectional"))
    )
    (net (code "58") (name "D25") (class "Default")
      (node (ref "R34") (pin "2") (pinfunction "2_2") (pintype "passive"))
      (node (ref "U1") (pin "37") (pinfunction "GPIO25_37") (pintype "bidirectional"))
    )
    (net (code "59") (name "GND") (class "Default")
      (node (ref "ANT1") (pin "P$1") (pinfunction "GND_P$1") (pintype "bidirectional"))
      (node (ref "ANT1") (pin "P$2") (pinfunction "GND_P$2") (pintype "bidirectional"))
      (node (ref "ANT2") (pin "2") (pinfunction "2_2") (pintype "passive"))
      (node (ref "ANT2") (pin "3") (pinfunction "2_3") (pintype "passive"))
      (node (ref "ANT2") (pin "4") (pinfunction "2_4") (pintype "passive"))
      (node (ref "ANT2") (pin "5") (pinfunction "2_5") (pintype "passive"))
      (node (ref "C1") (pin "2") (pinfunction "2_2") (pintype "passive"))
      (node (ref "C10") (pin "2") (pinfunction "2_2") (pintype "passive"))
      (node (ref "C11") (pin "2") (pinfunction "2_2") (pintype "passive"))
      (node (ref "C12") (pin "2") (pinfunction "2_2") (pintype "passive"))
      (node (ref "C13") (pin "2") (pinfunction "2_2") (pintype "passive"))
      (node (ref "C14") (pin "2") (pinfunction "2_2") (pintype "passive"))
      (node (ref "C15") (pin "2") (pinfunction "2_2") (pintype "passive"))
      (node (ref "C16") (pin "2") (pinfunction "2_2") (pintype "passive"))
      (node (ref "C2") (pin "1") (pinfunction "1_1") (pintype "passive"))
      (node (ref "C21") (pin "2") (pinfunction "2_2") (pintype "passive"))
      (node (ref "C24") (pin "2") (pinfunction "2_2") (pintype "passive"))
      (node (ref "C25") (pin "2") (pinfunction "2_2") (pintype "passive"))
      (node (ref "C26") (pin "1") (pinfunction "1_1") (pintype "passive"))
      (node (ref "C27") (pin "1") (pinfunction "1_1") (pintype "passive"))
      (node (ref "C28") (pin "1") (pinfunction "1_1") (pintype "passive"))
      (node (ref "C29") (pin "2") (pinfunction "2_2") (pintype "passive"))
      (node (ref "C3") (pin "2") (pinfunction "2_2") (pintype "passive"))
      (node (ref "C30") (pin "2") (pinfunction "2_2") (pintype "passive"))
      (node (ref "C31") (pin "1") (pinfunction "1_1") (pintype "passive"))
      (node (ref "C32") (pin "2") (pinfunction "2_2") (pintype "passive"))
      (node (ref "C33") (pin "1") (pinfunction "1_1") (pintype "passive"))
      (node (ref "C34") (pin "2") (pinfunction "2_2") (pintype "passive"))
      (node (ref "C35") (pin "2") (pinfunction "2_2") (pintype "passive"))
      (node (ref "C36") (pin "2") (pinfunction "2_2") (pintype "passive"))
      (node (ref "C37") (pin "2") (pinfunction "2_2") (pintype "passive"))
      (node (ref "C4") (pin "2") (pinfunction "2_2") (pintype "passive"))
      (node (ref "C5") (pin "2") (pinfunction "2_2") (pintype "passive"))
      (node (ref "C6") (pin "2") (pinfunction "2_2") (pintype "passive"))
      (node (ref "C7") (pin "2") (pinfunction "2_2") (pintype "passive"))
      (node (ref "C8") (pin "2") (pinfunction "2_2") (pintype "passive"))
      (node (ref "C9") (pin "2") (pinfunction "2_2") (pintype "passive"))
      (node (ref "D1") (pin "-") (pinfunction "-_-") (pintype "passive"))
      (node (ref "D3") (pin "-") (pinfunction "-_-") (pintype "passive"))
      (node (ref "IC1") (pin "3") (pinfunction "A0_3") (pintype "bidirectional"))
      (node (ref "IC1") (pin "4") (pinfunction "A1_4") (pintype "bidirectional"))
      (node (ref "IC1") (pin "5") (pinfunction "A2_5") (pintype "bidirectional"))
      (node (ref "IC1") (pin "8") (pinfunction "VSS_8") (pintype "bidirectional"))
      (node (ref "J1") (pin "1") (pinfunction "1_1") (pintype "bidirectional"))
      (node (ref "J10") (pin "1") (pinfunction "1_1") (pintype "bidirectional"))
      (node (ref "J11") (pin "1") (pinfunction "1_1") (pintype "bidirectional"))
      (node (ref "J12") (pin "1") (pinfunction "1_1") (pintype "bidirectional"))
      (node (ref "J13") (pin "3") (pinfunction "3_3") (pintype "bidirectional"))
      (node (ref "J14") (pin "A1") (pinfunction "A1_A1") (pintype "bidirectional"))
      (node (ref "J14") (pin "A12") (pinfunction "A12_A12") (pintype "bidirectional"))
      (node (ref "J14") (pin "B1") (pinfunction "B1_B1") (pintype "bidirectional"))
      (node (ref "J14") (pin "B12") (pinfunction "B12_B12") (pintype "bidirectional"))
      (node (ref "J14") (pin "P$1") (pinfunction "P$17_P$1") (pintype "bidirectional"))
      (node (ref "J14") (pin "P$2") (pinfunction "P$18_P$2") (pintype "bidirectional"))
      (node (ref "J14") (pin "P$3") (pinfunction "P$19_P$3") (pintype "bidirectional"))
      (node (ref "J14") (pin "P$4") (pinfunction "P$20_P$4") (pintype "bidirectional"))
      (node (ref "J18") (pin "1") (pinfunction "1_1") (pintype "passive"))
      (node (ref "J18") (pin "10") (pinfunction "10_10") (pintype "passive"))
      (node (ref "J18") (pin "11") (pinfunction "11_11") (pintype "passive"))
      (node (ref "J18") (pin "12") (pinfunction "12_12") (pintype "passive"))
      (node (ref "J18") (pin "2") (pinfunction "2_2") (pintype "passive"))
      (node (ref "J18") (pin "3") (pinfunction "3_3") (pintype "passive"))
      (node (ref "J18") (pin "4") (pinfunction "4_4") (pintype "passive"))
      (node (ref "J18") (pin "5") (pinfunction "5_5") (pintype "passive"))
      (node (ref "J18") (pin "6") (pinfunction "6_6") (pintype "passive"))
      (node (ref "J18") (pin "7") (pinfunction "7_7") (pintype "passive"))
      (node (ref "J18") (pin "8") (pinfunction "8_8") (pintype "passive"))
      (node (ref "J18") (pin "9") (pinfunction "9_9") (pintype "passive"))
      (node (ref "J2") (pin "1") (pinfunction "1_1") (pintype "passive"))
      (node (ref "J27") (pin "1") (pinfunction "1_1") (pintype "passive"))
      (node (ref "J27") (pin "10") (pinfunction "10_10") (pintype "passive"))
      (node (ref "J27") (pin "11") (pinfunction "11_11") (pintype "passive"))
      (node (ref "J27") (pin "12") (pinfunction "12_12") (pintype "passive"))
      (node (ref "J27") (pin "13") (pinfunction "13_13") (pintype "passive"))
      (node (ref "J27") (pin "14") (pinfunction "14_14") (pintype "passive"))
      (node (ref "J27") (pin "2") (pinfunction "2_2") (pintype "passive"))
      (node (ref "J27") (pin "3") (pinfunction "3_3") (pintype "passive"))
      (node (ref "J27") (pin "4") (pinfunction "4_4") (pintype "passive"))
      (node (ref "J27") (pin "5") (pinfunction "5_5") (pintype "passive"))
      (node (ref "J27") (pin "6") (pinfunction "6_6") (pintype "passive"))
      (node (ref "J27") (pin "7") (pinfunction "7_7") (pintype "passive"))
      (node (ref "J27") (pin "8") (pinfunction "8_8") (pintype "passive"))
      (node (ref "J27") (pin "9") (pinfunction "9_9") (pintype "passive"))
      (node (ref "J4") (pin "1") (pinfunction "1_1") (pintype "passive"))
      (node (ref "J46") (pin "1") (pinfunction "1_1") (pintype "passive"))
      (node (ref "J47") (pin "1") (pinfunction "1_1") (pintype "passive"))
      (node (ref "J49") (pin "1") (pinfunction "1_1") (pintype "passive"))
      (node (ref "J50") (pin "1") (pinfunction "1_1") (pintype "passive"))
      (node (ref "J6") (pin "1") (pinfunction "1_1") (pintype "bidirectional"))
      (node (ref "J7") (pin "1") (pinfunction "1_1") (pintype "bidirectional"))
      (node (ref "J8") (pin "1") (pinfunction "1_1") (pintype "bidirectional"))
      (node (ref "J9") (pin "1") (pinfunction "1_1") (pintype "bidirectional"))
      (node (ref "K2") (pin "2") (pinfunction "P$2_2") (pintype "bidirectional"))
      (node (ref "K3") (pin "2") (pinfunction "P$2_2") (pintype "bidirectional"))
      (node (ref "K4") (pin "2") (pinfunction "P$2_2") (pintype "bidirectional"))
      (node (ref "K5") (pin "2") (pinfunction "P$2_2") (pintype "bidirectional"))
      (node (ref "LCD1") (pin "1") (pinfunction "NC_1") (pintype "power_in"))
      (node (ref "LCD1") (pin "13") (pinfunction "GND2_13") (pintype "bidirectional"))
      (node (ref "LCD1") (pin "14") (pinfunction "NC1_14") (pintype "power_in"))
      (node (ref "LCD1") (pin "2") (pinfunction "GND_2") (pintype "power_in"))
      (node (ref "LCD1") (pin "5") (pinfunction "GND1_5") (pintype "power_in"))
      (node (ref "P1") (pin "P$1") (pinfunction "P$1_P$1") (pintype "bidirectional"))
      (node (ref "P10") (pin "P$1") (pinfunction "P$1_P$1") (pintype "bidirectional"))
      (node (ref "P14") (pin "P$1") (pinfunction "P$1_P$1") (pintype "bidirectional"))
      (node (ref "Q3") (pin "2") (pinfunction "E_2") (pintype "passive"))
      (node (ref "Q4") (pin "2") (pinfunction "E_2") (pintype "passive"))
      (node (ref "R12") (pin "2") (pinfunction "2_2") (pintype "passive"))
      (node (ref "R13") (pin "1") (pinfunction "1_1") (pintype "passive"))
      (node (ref "R22") (pin "2") (pinfunction "2_2") (pintype "passive"))
      (node (ref "R29") (pin "1") (pinfunction "1_1") (pintype "passive"))
      (node (ref "R45") (pin "1") (pinfunction "1_1") (pintype "passive"))
      (node (ref "R65") (pin "1") (pinfunction "1_1") (pintype "passive"))
      (node (ref "R73") (pin "2") (pinfunction "2_2") (pintype "passive"))
      (node (ref "R82") (pin "1") (pinfunction "1_1") (pintype "passive"))
      (node (ref "SW1") (pin "1") (pinfunction "1_1") (pintype "passive"))
      (node (ref "SW2") (pin "1") (pinfunction "1_1") (pintype "passive"))
      (node (ref "U1") (pin "19") (pinfunction "TESTEN_19") (pintype "bidirectional"))
      (node (ref "U1") (pin "EPAD") (pinfunction "GND_EPAD") (pintype "bidirectional"))
      (node (ref "U2") (pin "4") (pinfunction "GND_4") (pintype "bidirectional"))
      (node (ref "U3") (pin "1") (pinfunction "GND_1") (pintype "bidirectional"))
      (node (ref "U4") (pin "1") (pinfunction "GND_1") (pintype "power_in"))
      (node (ref "U4") (pin "17") (pinfunction "GND1_17") (pintype "bidirectional"))
      (node (ref "U5") (pin "5") (pinfunction "GND_5") (pintype "bidirectional"))
      (node (ref "U6") (pin "2") (pinfunction "GND_2") (pintype "bidirectional"))
      (node (ref "X1") (pin "2") (pinfunction "GND_2") (pintype "bidirectional"))
      (node (ref "X1") (pin "4") (pinfunction "GND_4") (pintype "bidirectional"))
    )
    (net (code "60") (name "GRE1") (class "Default")
      (node (ref "D5") (pin "K") (pinfunction "C_K") (pintype "passive"))
      (node (ref "IC1") (pin "11") (pinfunction "IO4_11") (pintype "bidirectional"))
    )
    (net (code "61") (name "GRE2") (class "Default")
      (node (ref "D9") (pin "K") (pinfunction "C_K") (pintype "passive"))
      (node (ref "IC1") (pin "14") (pinfunction "IO7_14") (pintype "bidirectional"))
    )
    (net (code "62") (name "IO2") (class "Default")
      (node (ref "SW3") (pin "1") (pinfunction "1_1") (pintype "passive"))
      (node (ref "U4") (pin "15") (pinfunction "IO2_15") (pintype "bidirectional"))
    )
    (net (code "63") (name "LCD_BLK") (class "Default")
      (node (ref "R19") (pin "1") (pinfunction "1_1") (pintype "passive"))
      (node (ref "U1") (pin "35") (pinfunction "GPIO23_35") (pintype "bidirectional"))
    )
    (net (code "64") (name "LCD_CS") (class "Default")
      (node (ref "LCD1") (pin "12") (pinfunction "CS_12") (pintype "bidirectional"))
      (node (ref "U1") (pin "28") (pinfunction "GPIO17_28") (pintype "bidirectional"))
    )
    (net (code "65") (name "LCD_DC") (class "Default")
      (node (ref "LCD1") (pin "7") (pinfunction "AO_7") (pintype "bidirectional"))
      (node (ref "U1") (pin "27") (pinfunction "GPIO16_27") (pintype "bidirectional"))
    )
    (net (code "66") (name "LCD_DIN") (class "Default")
      (node (ref "LCD1") (pin "8") (pinfunction "SDA_8") (pintype "bidirectional"))
      (node (ref "U1") (pin "30") (pinfunction "GPIO19_30") (pintype "bidirectional"))
    )
    (net (code "67") (name "LCD_RST") (class "Default")
      (node (ref "LCD1") (pin "6") (pinfunction "/RESET_6") (pintype "bidirectional"))
      (node (ref "U1") (pin "34") (pinfunction "GPIO22_34") (pintype "bidirectional"))
    )
    (net (code "68") (name "LCD_SCK") (class "Default")
      (node (ref "LCD1") (pin "9") (pinfunction "SCK_9") (pintype "bidirectional"))
      (node (ref "U1") (pin "29") (pinfunction "GPIO18_29") (pintype "bidirectional"))
    )
    (net (code "69") (name "LED-") (class "Default")
      (node (ref "LCD1") (pin "3") (pinfunction "LED-_3") (pintype "bidirectional"))
      (node (ref "R21") (pin "2") (pinfunction "2_2") (pintype "passive"))
    )
    (net (code "70") (name "Net-(ANT1-SIGNAL)") (class "Default")
      (node (ref "ANT1") (pin "P$3") (pinfunction "SIGNAL_P$3") (pintype "bidirectional"))
      (node (ref "ANT2") (pin "1") (pinfunction "1_1") (pintype "passive"))
      (node (ref "U4") (pin "18") (pinfunction "ANT_18") (pintype "bidirectional"))
    )
    (net (code "71") (name "Net-(D1-Pad+)") (class "Default")
      (node (ref "D1") (pin "+") (pinfunction "+_+") (pintype "passive"))
      (node (ref "R34") (pin "1") (pinfunction "1_1") (pintype "passive"))
    )
    (net (code "72") (name "Net-(D2-+)") (class "Default")
      (node (ref "D2") (pin "A") (pinfunction "+_A") (pintype "passive"))
      (node (ref "J3") (pin "2") (pinfunction "-_2") (pintype "bidirectional"))
      (node (ref "Q4") (pin "3") (pinfunction "C_3") (pintype "passive"))
    )
    (net (code "73") (name "Net-(D2--)") (class "Default")
      (node (ref "D2") (pin "C") (pinfunction "-_C") (pintype "passive"))
      (node (ref "J3") (pin "1") (pinfunction "+_1") (pintype "bidirectional"))
      (node (ref "R27") (pin "1") (pinfunction "1_1") (pintype "passive"))
    )
    (net (code "74") (name "Net-(D3-Pad+)") (class "Default")
      (node (ref "D3") (pin "+") (pinfunction "+_+") (pintype "passive"))
      (node (ref "R35") (pin "1") (pinfunction "1_1") (pintype "passive"))
    )
    (net (code "75") (name "Net-(D4-PadA)") (class "Default")
      (node (ref "D4") (pin "A") (pinfunction "A_A") (pintype "passive"))
      (node (ref "R75") (pin "1") (pinfunction "1_1") (pintype "passive"))
    )
    (net (code "76") (name "Net-(D5-PadA)") (class "Default")
      (node (ref "D5") (pin "A") (pinfunction "A_A") (pintype "passive"))
      (node (ref "R76") (pin "1") (pinfunction "1_1") (pintype "passive"))
    )
    (net (code "77") (name "Net-(D6-PadA)") (class "Default")
      (node (ref "D6") (pin "A") (pinfunction "A_A") (pintype "passive"))
      (node (ref "R77") (pin "1") (pinfunction "1_1") (pintype "passive"))
    )
    (net (code "78") (name "Net-(D7-PadA)") (class "Default")
      (node (ref "D7") (pin "A") (pinfunction "A_A") (pintype "passive"))
      (node (ref "R78") (pin "1") (pinfunction "1_1") (pintype "passive"))
    )
    (net (code "79") (name "Net-(D8-PadA)") (class "Default")
      (node (ref "D8") (pin "A") (pinfunction "A_A") (pintype "passive"))
      (node (ref "R79") (pin "1") (pinfunction "1_1") (pintype "passive"))
    )
    (net (code "80") (name "Net-(D9-PadA)") (class "Default")
      (node (ref "D9") (pin "A") (pinfunction "A_A") (pintype "passive"))
      (node (ref "R80") (pin "1") (pinfunction "1_1") (pintype "passive"))
    )
    (net (code "81") (name "Net-(IC1-RESET{slash})") (class "Default")
      (node (ref "IC1") (pin "15") (pinfunction "RESET/_15") (pintype "bidirectional"))
      (node (ref "R44") (pin "1") (pinfunction "1_1") (pintype "passive"))
    )
    (net (code "82") (name "Net-(J14-PadA5)") (class "Default")
      (node (ref "J14") (pin "A5") (pinfunction "A5_A5") (pintype "bidirectional"))
      (node (ref "R13") (pin "2") (pinfunction "2_2") (pintype "passive"))
    )
    (net (code "83") (name "Net-(J14-PadB5)") (class "Default")
      (node (ref "J14") (pin "B5") (pinfunction "B5_B5") (pintype "bidirectional"))
      (node (ref "R12") (pin "1") (pinfunction "1_1") (pintype "passive"))
    )
    (net (code "84") (name "Net-(K3-P$1)") (class "Default")
      (node (ref "K3") (pin "1") (pinfunction "P$1_1") (pintype "bidirectional"))
      (node (ref "R24") (pin "1") (pinfunction "1_1") (pintype "passive"))
      (node (ref "R25") (pin "2") (pinfunction "2_2") (pintype "passive"))
    )
    (net (code "85") (name "Net-(K4-P$1)") (class "Default")
      (node (ref "K4") (pin "1") (pinfunction "P$1_1") (pintype "bidirectional"))
      (node (ref "R25") (pin "1") (pinfunction "1_1") (pintype "passive"))
      (node (ref "R26") (pin "2") (pinfunction "2_2") (pintype "passive"))
    )
    (net (code "86") (name "Net-(K5-P$1)") (class "Default")
      (node (ref "K5") (pin "1") (pinfunction "P$1_1") (pintype "bidirectional"))
      (node (ref "R26") (pin "1") (pinfunction "1_1") (pintype "passive"))
    )
    (net (code "87") (name "Net-(Q3-B)") (class "Default")
      (node (ref "Q3") (pin "1") (pinfunction "B_1") (pintype "passive"))
      (node (ref "R19") (pin "2") (pinfunction "2_2") (pintype "passive"))
      (node (ref "R22") (pin "1") (pinfunction "1_1") (pintype "passive"))
    )
    (net (code "88") (name "Net-(Q3-C)") (class "Default")
      (node (ref "Q3") (pin "3") (pinfunction "C_3") (pintype "passive"))
      (node (ref "R21") (pin "1") (pinfunction "1_1") (pintype "passive"))
    )
    (net (code "89") (name "Net-(Q4-B)") (class "Default")
      (node (ref "Q4") (pin "1") (pinfunction "B_1") (pintype "passive"))
      (node (ref "R28") (pin "1") (pinfunction "1_1") (pintype "passive"))
      (node (ref "R29") (pin "2") (pinfunction "2_2") (pintype "passive"))
    )
    (net (code "90") (name "Net-(R18-Pad1)") (class "Default")
      (node (ref "R18") (pin "1") (pinfunction "1_1") (pintype "passive"))
      (node (ref "SW3") (pin "2") (pinfunction "2_2") (pintype "passive"))
    )
    (net (code "91") (name "Net-(U1-XIN)") (class "Default")
      (node (ref "C1") (pin "1") (pinfunction "1_1") (pintype "passive"))
      (node (ref "U1") (pin "20") (pinfunction "XIN_20") (pintype "bidirectional"))
      (node (ref "X1") (pin "1") (pinfunction "XIN_1") (pintype "bidirectional"))
    )
    (net (code "92") (name "Net-(U1-XOUT)") (class "Default")
      (node (ref "R2") (pin "2") (pinfunction "2_2") (pintype "passive"))
      (node (ref "U1") (pin "21") (pinfunction "XOUT_21") (pintype "bidirectional"))
    )
    (net (code "93") (name "Net-(U4-LPRXD)") (class "Default")
      (node (ref "R17") (pin "1") (pinfunction "1_1") (pintype "passive"))
      (node (ref "U4") (pin "10") (pinfunction "LPRXD_10") (pintype "bidirectional"))
    )
    (net (code "94") (name "Net-(U4-RST)") (class "Default")
      (node (ref "C37") (pin "1") (pinfunction "1_1") (pintype "passive"))
      (node (ref "R15") (pin "2") (pinfunction "2_2") (pintype "passive"))
      (node (ref "U4") (pin "16") (pinfunction "RST_16") (pintype "bidirectional"))
    )
    (net (code "95") (name "Net-(U6-FB)") (class "Default")
      (node (ref "R81") (pin "2") (pinfunction "2_2") (pintype "passive"))
      (node (ref "R82") (pin "2") (pinfunction "2_2") (pintype "passive"))
      (node (ref "U6") (pin "5") (pinfunction "FB_5") (pintype "bidirectional"))
    )
    (net (code "96") (name "Net-(U6-SW)") (class "Default")
      (node (ref "L1") (pin "1") (pinfunction "1_1") (pintype "passive"))
      (node (ref "U6") (pin "3") (pinfunction "SW_3") (pintype "bidirectional"))
    )
    (net (code "97") (name "Net-(X1-XOUT)") (class "Default")
      (node (ref "C2") (pin "2") (pinfunction "2_2") (pintype "passive"))
      (node (ref "R2") (pin "1") (pinfunction "1_1") (pintype "passive"))
      (node (ref "X1") (pin "3") (pinfunction "XOUT_3") (pintype "bidirectional"))
    )
    (net (code "98") (name "QSPI_CS") (class "Default")
      (node (ref "R6") (pin "1") (pinfunction "1_1") (pintype "passive"))
      (node (ref "R7") (pin "1") (pinfunction "1_1") (pintype "passive"))
      (node (ref "U1") (pin "56") (pinfunction "QSPI_~{CS}_56") (pintype "bidirectional"))
      (node (ref "U2") (pin "1") (pinfunction "/CS_1") (pintype "bidirectional"))
    )
    (net (code "99") (name "QSPI_D0") (class "Default")
      (node (ref "U1") (pin "53") (pinfunction "QSPI_SD0_53") (pintype "bidirectional"))
      (node (ref "U2") (pin "5") (pinfunction "DI(IO0)_5") (pintype "bidirectional"))
    )
    (net (code "100") (name "QSPI_D1") (class "Default")
      (node (ref "U1") (pin "55") (pinfunction "QSPI_SD1_55") (pintype "bidirectional"))
      (node (ref "U2") (pin "2") (pinfunction "DO(IO1)_2") (pintype "bidirectional"))
    )
    (net (code "101") (name "QSPI_D2") (class "Default")
      (node (ref "U1") (pin "54") (pinfunction "QSPI_SD2_54") (pintype "bidirectional"))
      (node (ref "U2") (pin "3") (pinfunction "/WP(IO2)_3") (pintype "bidirectional"))
    )
    (net (code "102") (name "QSPI_D3") (class "Default")
      (node (ref "U1") (pin "51") (pinfunction "QSPI_SD3_51") (pintype "bidirectional"))
      (node (ref "U2") (pin "7") (pinfunction "/HOLD/RESET(IO3)_7") (pintype "bidirectional"))
    )
    (net (code "103") (name "QSPI_SCK") (class "Default")
      (node (ref "U1") (pin "52") (pinfunction "QSPI_SCLK_52") (pintype "bidirectional"))
      (node (ref "U2") (pin "6") (pinfunction "CLK_6") (pintype "bidirectional"))
    )
    (net (code "104") (name "RED1") (class "Default")
      (node (ref "D7") (pin "K") (pinfunction "C_K") (pintype "passive"))
      (node (ref "IC1") (pin "9") (pinfunction "IO2_9") (pintype "bidirectional"))
    )
    (net (code "105") (name "RED2") (class "Default")
      (node (ref "D4") (pin "K") (pinfunction "C_K") (pintype "passive"))
      (node (ref "IC1") (pin "12") (pinfunction "IO5_12") (pintype "bidirectional"))
    )
    (net (code "106") (name "RESET") (class "Default")
      (node (ref "C4") (pin "1") (pinfunction "1_1") (pintype "passive"))
      (node (ref "R1") (pin "1") (pinfunction "1_1") (pintype "passive"))
      (node (ref "SW1") (pin "2") (pinfunction "2_2") (pintype "passive"))
      (node (ref "U1") (pin "26") (pinfunction "RUN_26") (pintype "bidirectional"))
    )
    (net (code "107") (name "RF_+5V") (class "Default")
      (node (ref "C27") (pin "2") (pinfunction "2_2") (pintype "passive"))
      (node (ref "C30") (pin "1") (pinfunction "1_1") (pintype "passive"))
      (node (ref "D11") (pin "-") (pinfunction "-_-") (pintype "passive"))
      (node (ref "U3") (pin "3") (pinfunction "VIN_3") (pintype "bidirectional"))
    )
    (net (code "108") (name "RF_3V3") (class "Default")
      (node (ref "C21") (pin "1") (pinfunction "1_1") (pintype "passive"))
      (node (ref "C28") (pin "2") (pinfunction "2_2") (pintype "passive"))
      (node (ref "C29") (pin "1") (pinfunction "1_1") (pintype "passive"))
      (node (ref "J2") (pin "2") (pinfunction "2_2") (pintype "passive"))
      (node (ref "P7") (pin "P$1") (pinfunction "P$1_P$1") (pintype "bidirectional"))
      (node (ref "R15") (pin "1") (pinfunction "1_1") (pintype "passive"))
      (node (ref "R18") (pin "2") (pinfunction "2_2") (pintype "passive"))
      (node (ref "U3") (pin "2") (pinfunction "VOUT_2") (pintype "bidirectional"))
      (node (ref "U3") (pin "4") (pinfunction "TAB_4") (pintype "bidirectional"))
      (node (ref "U4") (pin "9") (pinfunction "VCC_9") (pintype "power_in"))
    )
    (net (code "109") (name "RF_RX") (class "Default")
      (node (ref "J2") (pin "3") (pinfunction "3_3") (pintype "passive"))
      (node (ref "U4") (pin "12") (pinfunction "RXD0_12") (pintype "bidirectional"))
    )
    (net (code "110") (name "RF_SWCLK") (class "Default")
      (node (ref "P9") (pin "P$1") (pinfunction "P$1_P$1") (pintype "bidirectional"))
      (node (ref "U4") (pin "7") (pinfunction "SWCLK_7") (pintype "bidirectional"))
    )
    (net (code "111") (name "RF_SWDIO") (class "Default")
      (node (ref "P8") (pin "P$1") (pinfunction "P$1_P$1") (pintype "bidirectional"))
      (node (ref "U4") (pin "8") (pinfunction "SWDIO_8") (pintype "bidirectional"))
    )
    (net (code "112") (name "RF_TX") (class "Default")
      (node (ref "J2") (pin "4") (pinfunction "4_4") (pintype "passive"))
      (node (ref "R16") (pin "1") (pinfunction "1_1") (pintype "passive"))
      (node (ref "U4") (pin "11") (pinfunction "TXD_11") (pintype "bidirectional"))
    )
    (net (code "113") (name "RP_D0{slash}TX0") (class "Default")
      (node (ref "Q8") (pin "2") (pinfunction "S_2") (pintype "passive"))
      (node (ref "R20") (pin "1") (pinfunction "1_1") (pintype "passive"))
      (node (ref "U1") (pin "2") (pinfunction "GPIO0_2") (pintype "bidirectional"))
    )
    (net (code "114") (name "RP_D0{slash}TX0_H") (class "Default")
      (node (ref "J9") (pin "3") (pinfunction "3_3") (pintype "bidirectional"))
      (node (ref "Q8") (pin "3") (pinfunction "D_3") (pintype "passive"))
      (node (ref "R30") (pin "1") (pinfunction "1_1") (pintype "passive"))
    )
    (net (code "115") (name "RP_D1{slash}RX0") (class "Default")
      (node (ref "Q9") (pin "2") (pinfunction "S_2") (pintype "passive"))
      (node (ref "R31") (pin "1") (pinfunction "1_1") (pintype "passive"))
      (node (ref "U1") (pin "3") (pinfunction "GPIO1_3") (pintype "bidirectional"))
    )
    (net (code "116") (name "RP_D1{slash}RX0_H") (class "Default")
      (node (ref "J9") (pin "4") (pinfunction "4_4") (pintype "bidirectional"))
      (node (ref "Q9") (pin "3") (pinfunction "D_3") (pintype "passive"))
      (node (ref "R32") (pin "1") (pinfunction "1_1") (pintype "passive"))
    )
    (net (code "117") (name "RS_RX") (class "Default")
      (node (ref "J24") (pin "1") (pinfunction "1_1") (pintype "passive"))
      (node (ref "R71") (pin "1") (pinfunction "1_1") (pintype "passive"))
      (node (ref "U5") (pin "1") (pinfunction "RO_1") (pintype "bidirectional"))
    )
    (net (code "118") (name "RS_TX") (class "Default")
      (node (ref "J25") (pin "1") (pinfunction "1_1") (pintype "passive"))
      (node (ref "R14") (pin "1") (pinfunction "1_1") (pintype "passive"))
      (node (ref "U5") (pin "4") (pinfunction "DI_4") (pintype "bidirectional"))
    )
    (net (code "119") (name "SWCLK") (class "Default")
      (node (ref "P11") (pin "P$1") (pinfunction "P$1_P$1") (pintype "bidirectional"))
      (node (ref "U1") (pin "24") (pinfunction "SWCLK_24") (pintype "bidirectional"))
    )
    (net (code "120") (name "SWDIO") (class "Default")
      (node (ref "P12") (pin "P$1") (pinfunction "P$1_P$1") (pintype "bidirectional"))
      (node (ref "U1") (pin "25") (pinfunction "SWDIO_25") (pintype "bidirectional"))
    )
    (net (code "121") (name "USB_D+") (class "Default")
      (node (ref "P3") (pin "P$1") (pinfunction "P$1_P$1") (pintype "bidirectional"))
      (node (ref "R11") (pin "2") (pinfunction "2_2") (pintype "passive"))
      (node (ref "U1") (pin "47") (pinfunction "USB_D+_47") (pintype "bidirectional"))
    )
    (net (code "122") (name "USB_D-") (class "Default")
      (node (ref "P4") (pin "P$1") (pinfunction "P$1_P$1") (pintype "bidirectional"))
      (node (ref "R10") (pin "2") (pinfunction "2_2") (pintype "passive"))
      (node (ref "U1") (pin "46") (pinfunction "USB_D-_46") (pintype "bidirectional"))
    )
    (net (code "123") (name "YEL1") (class "Default")
      (node (ref "D6") (pin "K") (pinfunction "C_K") (pintype "passive"))
      (node (ref "IC1") (pin "10") (pinfunction "IO3_10") (pintype "bidirectional"))
    )
    (net (code "124") (name "YEL2") (class "Default")
      (node (ref "D8") (pin "K") (pinfunction "C_K") (pintype "passive"))
      (node (ref "IC1") (pin "13") (pinfunction "IO6_13") (pintype "bidirectional"))
    )
    (net (code "125") (name "unconnected-(IC1-IO0-Pad6)") (class "Default")
      (node (ref "IC1") (pin "6") (pinfunction "IO0_6") (pintype "bidirectional"))
    )
    (net (code "126") (name "unconnected-(IC1-IO1-Pad7)") (class "Default")
      (node (ref "IC1") (pin "7") (pinfunction "IO1_7") (pintype "bidirectional"))
    )
    (net (code "127") (name "unconnected-(J1-Pad3)") (class "Default")
      (node (ref "J1") (pin "3") (pinfunction "3_3") (pintype "bidirectional"))
    )
    (net (code "128") (name "unconnected-(J6-Pad3)") (class "Default")
      (node (ref "J6") (pin "3") (pinfunction "3_3") (pintype "bidirectional"))
    )
    (net (code "129") (name "unconnected-(J7-Pad3)") (class "Default")
      (node (ref "J7") (pin "3") (pinfunction "3_3") (pintype "bidirectional"))
    )
    (net (code "130") (name "unconnected-(J8-Pad3)") (class "Default")
      (node (ref "J8") (pin "3") (pinfunction "3_3") (pintype "bidirectional"))
    )
    (net (code "131") (name "unconnected-(J14-PadA8)") (class "Default")
      (node (ref "J14") (pin "A8") (pinfunction "A8_A8") (pintype "bidirectional"))
    )
    (net (code "132") (name "unconnected-(J14-PadB8)") (class "Default")
      (node (ref "J14") (pin "B8") (pinfunction "B8_B8") (pintype "bidirectional"))
    )
    (net (code "133") (name "unconnected-(U4-IO4-Pad5)") (class "Default")
      (node (ref "U4") (pin "5") (pinfunction "IO4_5") (pintype "bidirectional"))
    )
    (net (code "134") (name "unconnected-(U4-IO5-Pad6)") (class "Default")
      (node (ref "U4") (pin "6") (pinfunction "IO5_6") (pintype "bidirectional"))
    )
    (net (code "135") (name "unconnected-(U4-IO8-Pad2)") (class "Default")
      (node (ref "U4") (pin "2") (pinfunction "IO8_2") (pintype "bidirectional"))
    )
    (net (code "136") (name "unconnected-(U4-IO9-Pad4)") (class "Default")
      (node (ref "U4") (pin "4") (pinfunction "IO9_4") (pintype "bidirectional"))
    )
    (net (code "137") (name "unconnected-(U4-IO11-Pad3)") (class "Default")
      (node (ref "U4") (pin "3") (pinfunction "IO11_3") (pintype "bidirectional"))
    )
    (net (code "138") (name "unconnected-(U4-IO14-Pad14)") (class "Default")
      (node (ref "U4") (pin "14") (pinfunction "IO14_14") (pintype "bidirectional"))
    )
    (net (code "139") (name "unconnected-(U4-IO15-Pad13)") (class "Default")
      (node (ref "U4") (pin "13") (pinfunction "IO15_13") (pintype "bidirectional"))
    )
  )
)
